# node24-stm32f765bit6.net
KiCad netlist of a schematic drawn in Altium Designer
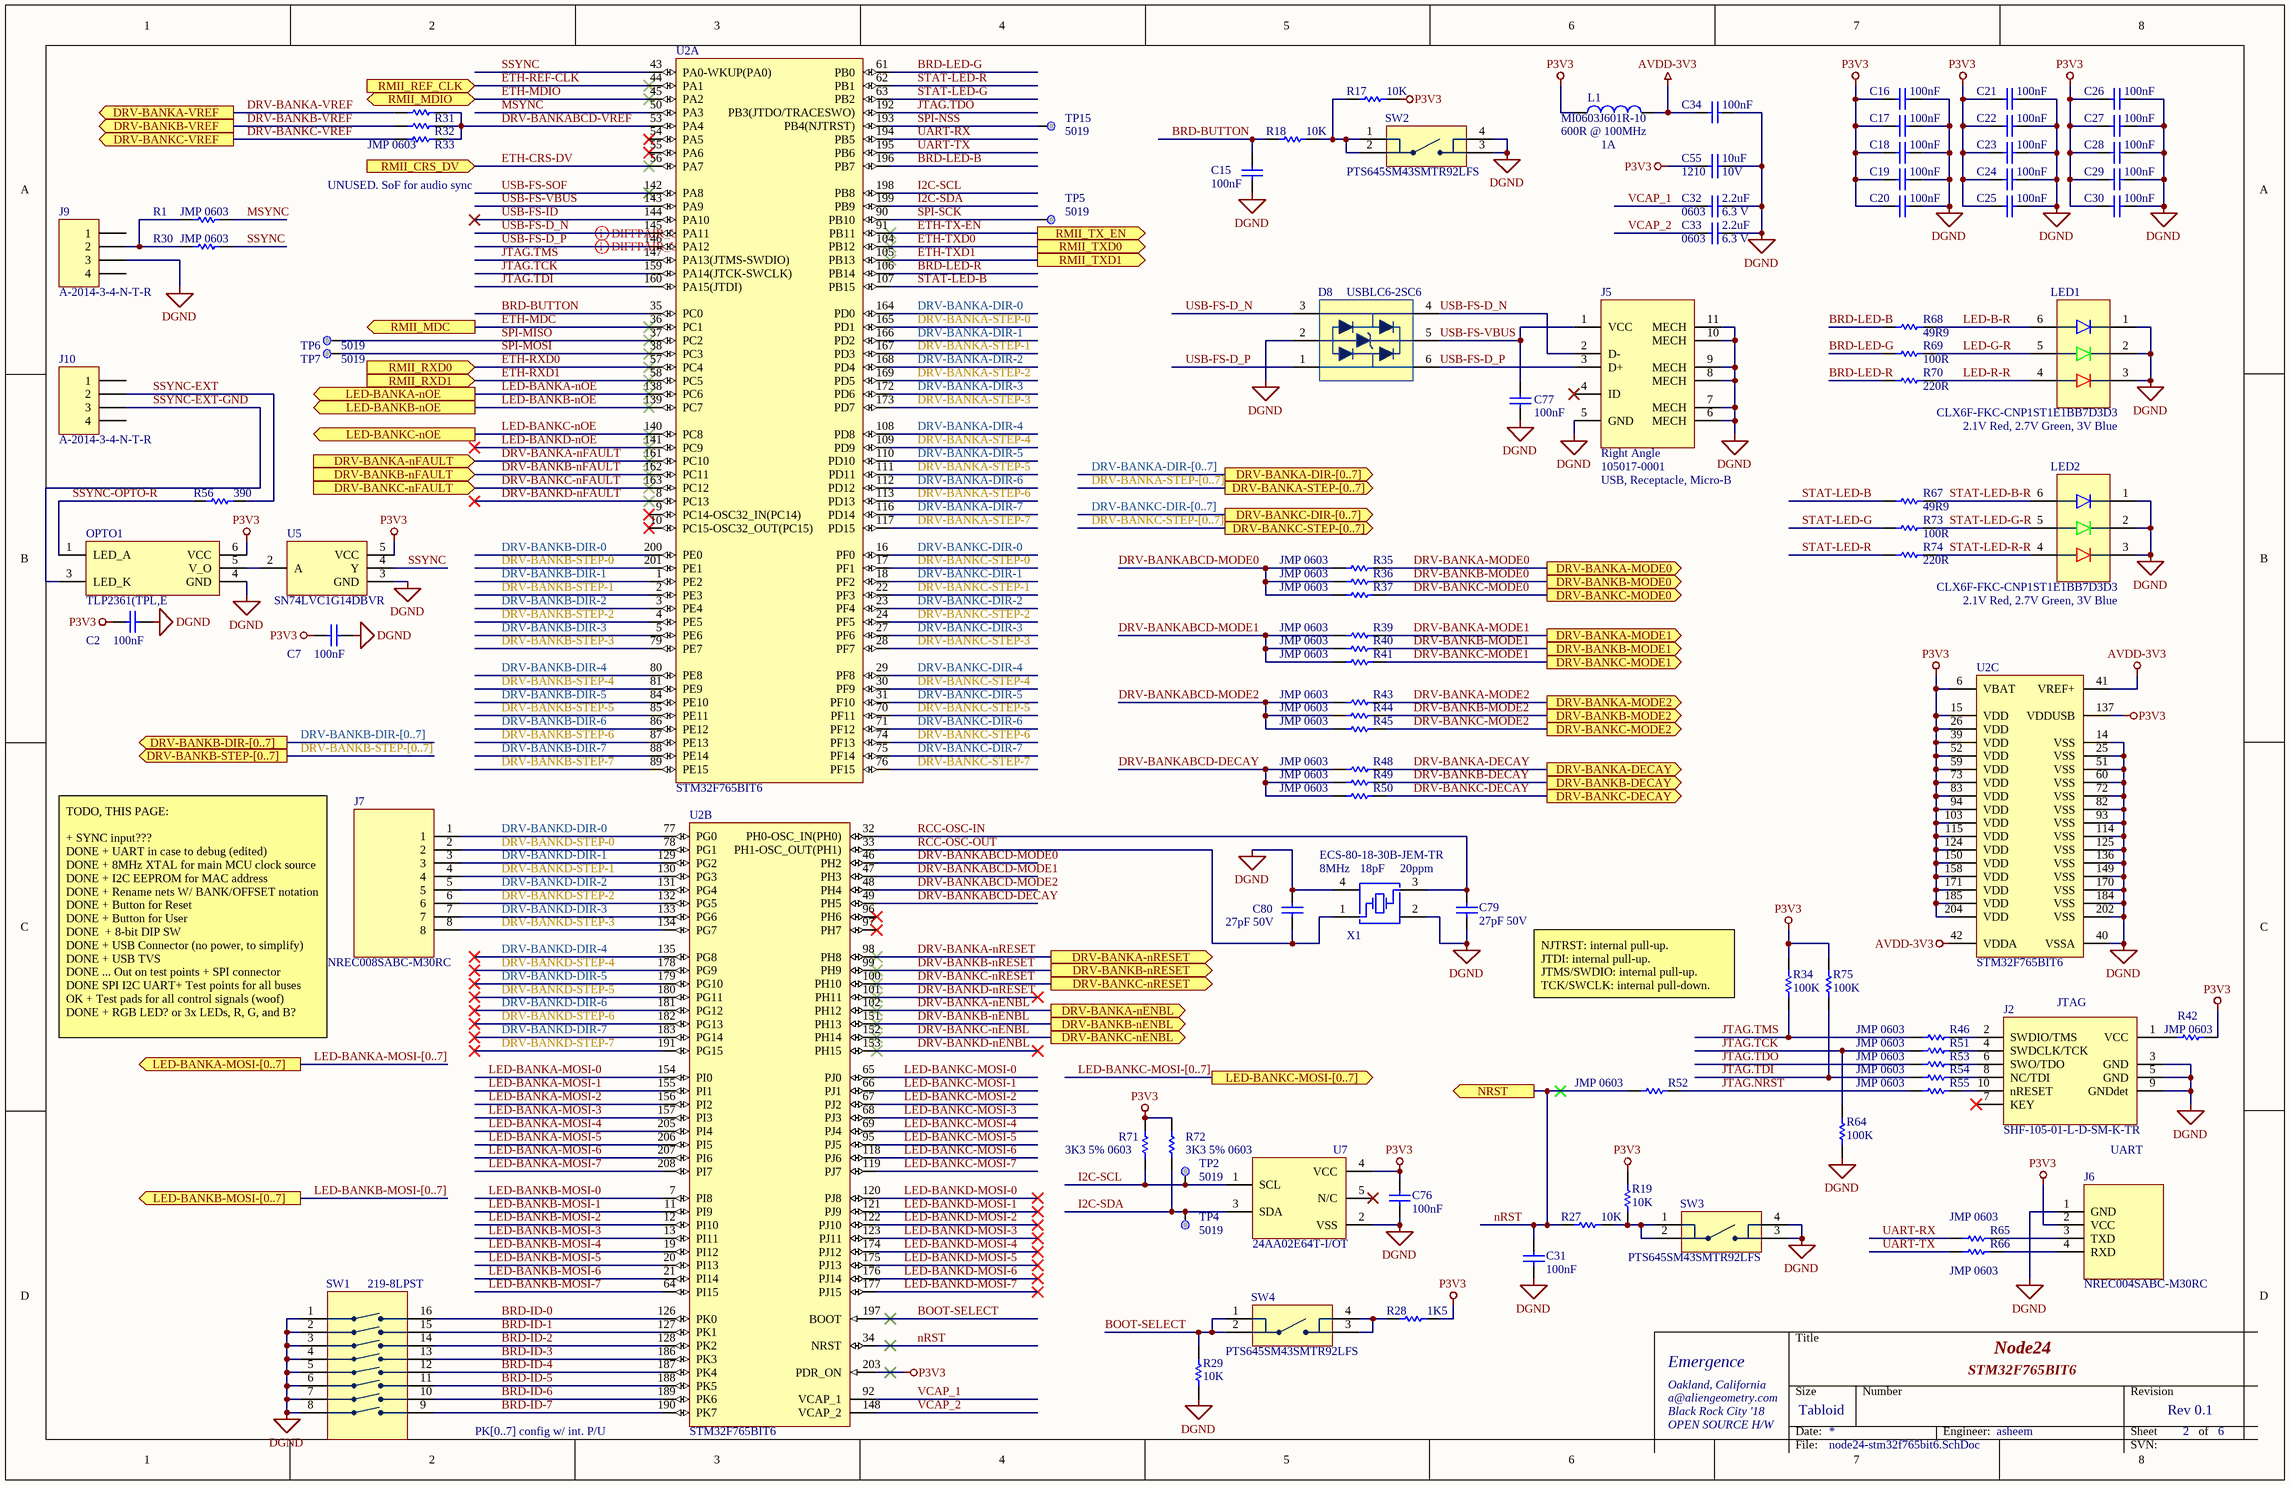
[diagram p0: node24-stm32f765bit6.SchDoc]

(export (version "E")
  (design (tool "Eeschema 10.0.6"))
  (components
    (comp (ref "C2")
      (value "100nF")
      (footprint "CAPC0603(1608)100_L")
      (description "CAP 100nF 50V ±20% 0603 (1608 Metric) Thickness 1mm SMD")
      (fields (field (name "TOLERANCE") "Â±20%"))
      (libsource (lib "Altium Content Vault") (part "CAP"))
    )
    (comp (ref "C7")
      (value "100nF")
      (footprint "CAPC0603(1608)100_L")
      (description "CAP 100nF 50V ±20% 0603 (1608 Metric) Thickness 1mm SMD")
      (fields (field (name "TOLERANCE") "Â±20%"))
      (libsource (lib "Altium Content Vault") (part "CAP"))
    )
    (comp (ref "C15")
      (value "100nF")
      (footprint "CAPC0603(1608)100_L")
      (description "CAP 100nF 50V ±20% 0603 (1608 Metric) Thickness 1mm SMD")
      (fields (field (name "TOLERANCE") "Â±20%"))
      (libsource (lib "Altium Content Vault") (part "CAP"))
    )
    (comp (ref "C16")
      (value "100nF")
      (footprint "CAPC0603(1608)100_L")
      (description "CAP 100nF 50V ±20% 0603 (1608 Metric) Thickness 1mm SMD")
      (fields (field (name "TOLERANCE") "Â±20%"))
      (libsource (lib "Altium Content Vault") (part "CAP"))
    )
    (comp (ref "C17")
      (value "100nF")
      (footprint "CAPC0603(1608)100_L")
      (description "CAP 100nF 50V ±20% 0603 (1608 Metric) Thickness 1mm SMD")
      (fields (field (name "TOLERANCE") "Â±20%"))
      (libsource (lib "Altium Content Vault") (part "CAP"))
    )
    (comp (ref "C18")
      (value "100nF")
      (footprint "CAPC0603(1608)100_L")
      (description "CAP 100nF 50V ±20% 0603 (1608 Metric) Thickness 1mm SMD")
      (fields (field (name "TOLERANCE") "Â±20%"))
      (libsource (lib "Altium Content Vault") (part "CAP"))
    )
    (comp (ref "C19")
      (value "100nF")
      (footprint "CAPC0603(1608)100_L")
      (description "CAP 100nF 50V ±20% 0603 (1608 Metric) Thickness 1mm SMD")
      (fields (field (name "TOLERANCE") "Â±20%"))
      (libsource (lib "Altium Content Vault") (part "CAP"))
    )
    (comp (ref "C20")
      (value "100nF")
      (footprint "CAPC0603(1608)100_L")
      (description "CAP 100nF 50V ±20% 0603 (1608 Metric) Thickness 1mm SMD")
      (fields (field (name "TOLERANCE") "Â±20%"))
      (libsource (lib "Altium Content Vault") (part "CAP"))
    )
    (comp (ref "C21")
      (value "100nF")
      (footprint "CAPC0603(1608)100_L")
      (description "CAP 100nF 50V ±20% 0603 (1608 Metric) Thickness 1mm SMD")
      (fields (field (name "TOLERANCE") "Â±20%"))
      (libsource (lib "Altium Content Vault") (part "CAP"))
    )
    (comp (ref "C22")
      (value "100nF")
      (footprint "CAPC0603(1608)100_L")
      (description "CAP 100nF 50V ±20% 0603 (1608 Metric) Thickness 1mm SMD")
      (fields (field (name "TOLERANCE") "Â±20%"))
      (libsource (lib "Altium Content Vault") (part "CAP"))
    )
    (comp (ref "C23")
      (value "100nF")
      (footprint "CAPC0603(1608)100_L")
      (description "CAP 100nF 50V ±20% 0603 (1608 Metric) Thickness 1mm SMD")
      (fields (field (name "TOLERANCE") "Â±20%"))
      (libsource (lib "Altium Content Vault") (part "CAP"))
    )
    (comp (ref "C24")
      (value "100nF")
      (footprint "CAPC0603(1608)100_L")
      (description "CAP 100nF 50V ±20% 0603 (1608 Metric) Thickness 1mm SMD")
      (fields (field (name "TOLERANCE") "Â±20%"))
      (libsource (lib "Altium Content Vault") (part "CAP"))
    )
    (comp (ref "C25")
      (value "100nF")
      (footprint "CAPC0603(1608)100_L")
      (description "CAP 100nF 50V ±20% 0603 (1608 Metric) Thickness 1mm SMD")
      (fields (field (name "TOLERANCE") "Â±20%"))
      (libsource (lib "Altium Content Vault") (part "CAP"))
    )
    (comp (ref "C26")
      (value "100nF")
      (footprint "CAPC0603(1608)100_L")
      (description "CAP 100nF 50V ±20% 0603 (1608 Metric) Thickness 1mm SMD")
      (fields (field (name "TOLERANCE") "Â±20%"))
      (libsource (lib "Altium Content Vault") (part "CAP"))
    )
    (comp (ref "C27")
      (value "100nF")
      (footprint "CAPC0603(1608)100_L")
      (description "CAP 100nF 50V ±20% 0603 (1608 Metric) Thickness 1mm SMD")
      (fields (field (name "TOLERANCE") "Â±20%"))
      (libsource (lib "Altium Content Vault") (part "CAP"))
    )
    (comp (ref "C28")
      (value "100nF")
      (footprint "CAPC0603(1608)100_L")
      (description "CAP 100nF 50V ±20% 0603 (1608 Metric) Thickness 1mm SMD")
      (fields (field (name "TOLERANCE") "Â±20%"))
      (libsource (lib "Altium Content Vault") (part "CAP"))
    )
    (comp (ref "C29")
      (value "100nF")
      (footprint "CAPC0603(1608)100_L")
      (description "CAP 100nF 50V ±20% 0603 (1608 Metric) Thickness 1mm SMD")
      (fields (field (name "TOLERANCE") "Â±20%"))
      (libsource (lib "Altium Content Vault") (part "CAP"))
    )
    (comp (ref "C30")
      (value "100nF")
      (footprint "CAPC0603(1608)100_L")
      (description "CAP 100nF 50V ±20% 0603 (1608 Metric) Thickness 1mm SMD")
      (fields (field (name "TOLERANCE") "Â±20%"))
      (libsource (lib "Altium Content Vault") (part "CAP"))
    )
    (comp (ref "C31")
      (value "100nF")
      (footprint "CAPC0603(1608)100_L")
      (description "CAP 100nF 50V ±20% 0603 (1608 Metric) Thickness 1mm SMD")
      (fields (field (name "TOLERANCE") "Â±20%"))
      (libsource (lib "Altium Content Vault") (part "CAP"))
    )
    (comp (ref "C32")
      (value "2.2uF")
      (footprint "CAPC0603(1608)100_M")
      (description "CAP 2.2uF 6.3V ±20% 0603 (1608 Metric) Thickness 1mm SMD")
      (fields
        (field (name "TOLERANCE") "Â±20%")
        (field (name "CASE-EIA") "0603")
        (field (name "RATED VOLTAGE") "6.3 V")
        (field (name "Comment") "2.2uF 6.3V")
      )
      (libsource (lib "Altium Content Vault") (part "CAP"))
    )
    (comp (ref "C33")
      (value "2.2uF")
      (footprint "CAPC0603(1608)100_M")
      (description "CAP 2.2uF 6.3V ±20% 0603 (1608 Metric) Thickness 1mm SMD")
      (fields
        (field (name "TOLERANCE") "Â±20%")
        (field (name "CASE-EIA") "0603")
        (field (name "RATED VOLTAGE") "6.3 V")
        (field (name "Comment") "2.2uF 6.3V")
      )
      (libsource (lib "Altium Content Vault") (part "CAP"))
    )
    (comp (ref "C34")
      (value "100nF")
      (footprint "CAPC0603(1608)100_L")
      (description "CAP 100nF 50V ±20% 0603 (1608 Metric) Thickness 1mm SMD")
      (fields (field (name "TOLERANCE") "Â±20%"))
      (libsource (lib "Altium Content Vault") (part "CAP"))
    )
    (comp (ref "C55")
      (value "CAP_CER_10UF_1210_CL32B106KPINNNE")
      (footprint "1210C")
      (description "Cap Ceramic 10uF 10V X7R 10% SMD 1210 125C Embossed T/R")
      (fields
        (field (name "MANUFACTURER") "Samsung")
        (field (name "MANUFACTURER PART NUMBER") "CL32B106KPINNNE")
        (field (name "CAPACITANCE") "10uF")
        (field (name "CASE/PACKAGE") "1210")
        (field (name "VOLTAGE RATING") "10V")
      )
      (libsource (lib "node") (part "CAP_CER_10UF_1210_CL32B106KPINNNE"))
    )
    (comp (ref "C76")
      (value "100nF")
      (footprint "CAPC0603(1608)100_L")
      (description "CAP 100nF 50V ±20% 0603 (1608 Metric) Thickness 1mm SMD")
      (fields (field (name "TOLERANCE") "Â±20%"))
      (libsource (lib "Altium Content Vault") (part "CAP"))
    )
    (comp (ref "C77")
      (value "100nF")
      (footprint "CAPC0603(1608)100_L")
      (description "CAP 100nF 50V ±20% 0603 (1608 Metric) Thickness 1mm SMD")
      (fields (field (name "TOLERANCE") "Â±20%"))
      (libsource (lib "Altium Content Vault") (part "CAP"))
    )
    (comp (ref "C79")
      (value "27pF 50V")
      (footprint "CAPC0603(1608)100_L")
      (description "CAP 27pF 50V ±5% 0603 (1608 Metric) Thickness 1mm SMD")
      (fields (field (name "TOLERANCE") "Â±5%"))
      (libsource (lib "Altium Content Vault") (part "CAP"))
    )
    (comp (ref "C80")
      (value "27pF 50V")
      (footprint "CAPC0603(1608)100_L")
      (description "CAP 27pF 50V ±5% 0603 (1608 Metric) Thickness 1mm SMD")
      (fields (field (name "TOLERANCE") "Â±5%"))
      (libsource (lib "Altium Content Vault") (part "CAP"))
    )
    (comp (ref "D8")
      (value "TVS DIODE 5.25V 17V SOT23-6")
      (footprint "SOT23-6L")
      (description "TVS DIODE 5.25VWM 17VC SOT23-6")
      (fields
        (field (name "MANUFACTURER") "STMicroelectronics")
        (field (name "MANUFACTURER PART NUMBER") "USBLC6-2SC6")
      )
      (libsource (lib "node") (part "TVS_5.25_USB_ST_USBLC6-2SC6"))
    )
    (comp (ref "J2")
      (value "CONN_HDR_2X5_V_M_SM_50MIL_SAMTEC_SHF-105-01-L-D-SM-K-TR")
      (footprint "CONN_SAMTEC_HDR_50MIL_10POS_SHRD_SM_SHF-105-01-L-D-SM")
      (description "Conn Shrouded Header HDR 10 POS 1.27mm Solder ST SMD T/R")
      (fields
        (field (name "MANUFACTURER") "Samtec")
        (field (name "MANUFACTURER PART NUMBER") "SHF-105-01-L-D-SM-K-TR")
      )
      (libsource (lib "node") (part "CONN_HDR_2X5_V_M_SM_50MIL_SAMTEC_SHF-105-01-L-D-SM-K-TR"))
    )
    (comp (ref "J5")
      (value "CONN_USB_MICRO-B_RA_SMD_MOLEX_105017-0001")
      (footprint "CONN_MOLEX_USB_MICRO_B_SMD_RA_1050170001")
      (description "USB - micro B  Receptacle Connector 5 Position Board Cutout, Surface Mount, Right Angle")
      (fields
        (field (name "MANUFACTURER") "Molex")
        (field (name "ORIENTATION") "Right Angle")
        (field (name "MANUFACTURER PART NUMBER") "105017-0001")
        (field (name "CONNECTOR TYPE") "USB, Receptacle, Micro-B")
      )
      (libsource (lib "node") (part "CONN_USB_MICRO-B_RA_SMD_MOLEX_105017-0001"))
    )
    (comp (ref "J6")
      (value "CONN_HDR_1X4_V_SMT_NREC004SABC-M30RC")
      (footprint "HDR_1X4_2R54_V_M_SMT")
      (description "CONN HEADER .100\" SNGL SMD 4POS")
      (fields
        (field (name "MANUFACTURER") "Sullins")
        (field (name "MANUFACTURER PART NUMBER") "NREC004SABC-M30RC")
      )
      (libsource (lib "node") (part "CONN_HDR_1X4_V_SMT_NREC004SABC-M30RC"))
    )
    (comp (ref "J7")
      (value "CONN_HDR_1X8_V_M_SMT_NREC008SABC-M30RC")
      (footprint "HDR_1X8_2R54_V_M_SMT")
      (description "8 Positions Header, Unshrouded Connector 0.100\" (2.54mm) Surface Mount Tin")
      (fields
        (field (name "MANUFACTURER") "Sullins")
        (field (name "MANUFACTURER PART NUMBER") "NREC008SABC-M30RC")
      )
      (libsource (lib "node") (part "CONN_HDR_1X8_V_M_SMT_NREC008SABC-M30RC"))
    )
    (comp (ref "J9")
      (value "CONN_ASSMANN_JACK_MOD_4P4C_A-2014-3-4-N-T-R")
      (footprint "CON_JACK_MOD_4P4C_ASSMANN_A-2014-3-4-N-T-R")
      (description "CONN MOD JACK 4P4C VERT")
      (fields
        (field (name "MANUFACTURER") "Assmann")
        (field (name "MANUFACTURER PART NUMBER") "A-2014-3-4-N-T-R")
      )
      (libsource (lib "node") (part "CONN_ASSMANN_JACK_MOD_4P4C_A-2014-3-4-N-T-R"))
    )
    (comp (ref "J10")
      (value "CONN_ASSMANN_JACK_MOD_4P4C_A-2014-3-4-N-T-R")
      (footprint "CON_JACK_MOD_4P4C_ASSMANN_A-2014-3-4-N-T-R")
      (description "CONN MOD JACK 4P4C VERT")
      (fields
        (field (name "MANUFACTURER") "Assmann")
        (field (name "MANUFACTURER PART NUMBER") "A-2014-3-4-N-T-R")
      )
      (libsource (lib "node") (part "CONN_ASSMANN_JACK_MOD_4P4C_A-2014-3-4-N-T-R"))
    )
    (comp (ref "L1")
      (value "BEAD_LAIRD_MI0603J601R-10")
      (footprint "0603L")
      (description "FERRITE BEAD 600 OHM 0603")
      (fields
        (field (name "MANUFACTURER") "Laird")
        (field (name "MANUFACTURER PART NUMBER") "MI0603J601R-10")
        (field (name "MAX DC CURRENT") "1A")
        (field (name "IMPEDANCE") "600R @ 100MHz")
      )
      (libsource (lib "node") (part "BEAD_LAIRD_MI0603J601R-10"))
    )
    (comp (ref "LED1")
      (value "LED_RGB_SMD_CLX6F-FKC-CNP1ST1E1BB7D3D3")
      (footprint "LED_6PLCC_RGB")
      (description "LED RGB IPX8 6PLCC 3.5X3.4X2.8MM")
      (fields
        (field (name "MANUFACTURER") "Cree")
        (field (name "FORWARD VOLTAGE") "2.1V Red, 2.7V Green, 3V Blue")
        (field (name "MANUFACTURER PART NUMBER") "CLX6F-FKC-CNP1ST1E1BB7D3D3")
      )
      (libsource (lib "node") (part "LED_RGB_SMD_CLX6F-FKC-CNP1ST1E1BB7D3D3"))
    )
    (comp (ref "LED2")
      (value "LED_RGB_SMD_CLX6F-FKC-CNP1ST1E1BB7D3D3")
      (footprint "LED_6PLCC_RGB")
      (description "LED RGB IPX8 6PLCC 3.5X3.4X2.8MM")
      (fields
        (field (name "MANUFACTURER") "Cree")
        (field (name "FORWARD VOLTAGE") "2.1V Red, 2.7V Green, 3V Blue")
        (field (name "MANUFACTURER PART NUMBER") "CLX6F-FKC-CNP1ST1E1BB7D3D3")
      )
      (libsource (lib "node") (part "LED_RGB_SMD_CLX6F-FKC-CNP1ST1E1BB7D3D3"))
    )
    (comp (ref "OPTO1")
      (value "OPTO_TOSHIBA_LOGIC_PUSHPULL_TLP2361(TPL,E")
      (footprint "SO-5")
      (description "Optocoupler Logic-Out Totem-Pole DC-IN 1-CH 5-Pin SO T/R")
      (fields
        (field (name "MANUFACTURER") "Toshiba")
        (field (name "MANUFACTURER PART NUMBER") "TLP2361(TPL,E")
      )
      (libsource (lib "node") (part "OPTO_TOSHIBA_LOGIC_PUSHPULL_TLP2361(TPL,E"))
    )
    (comp (ref "R1")
      (value "JMP 0603")
      (footprint "RESC0603(1608)_L")
      (description "Jumper 0603 (1608 Metric)")
      (fields (field (name "POWER") "None"))
      (libsource (lib "Altium Content Vault") (part "RES"))
    )
    (comp (ref "R17")
      (value "10K")
      (footprint "RESC0603(1608)_L")
      (description "10K 0.1W 1% 0603 (1608 Metric)  SMD")
      (fields (field (name "POWER") "0.1 W") (field (name "TOLERANCE") "1 %"))
      (libsource (lib "Altium Content Vault") (part "RES"))
    )
    (comp (ref "R18")
      (value "10K")
      (footprint "RESC0603(1608)_L")
      (description "10K 0.1W 1% 0603 (1608 Metric)  SMD")
      (fields (field (name "POWER") "0.1 W") (field (name "TOLERANCE") "1 %"))
      (libsource (lib "Altium Content Vault") (part "RES"))
    )
    (comp (ref "R19")
      (value "10K")
      (footprint "RESC0603(1608)_L")
      (description "10K 0.1W 1% 0603 (1608 Metric)  SMD")
      (fields (field (name "POWER") "0.1 W") (field (name "TOLERANCE") "1 %"))
      (libsource (lib "Altium Content Vault") (part "RES"))
    )
    (comp (ref "R27")
      (value "10K")
      (footprint "RESC0603(1608)_L")
      (description "10K 0.1W 1% 0603 (1608 Metric)  SMD")
      (fields (field (name "POWER") "0.1 W") (field (name "TOLERANCE") "1 %"))
      (libsource (lib "Altium Content Vault") (part "RES"))
    )
    (comp (ref "R28")
      (value "1K5")
      (footprint "RESC0603(1608)_L")
      (description "1K5 0.1W 1% 0603 (1608 Metric)  SMD")
      (fields (field (name "POWER") "0.1 W") (field (name "TOLERANCE") "1 %"))
      (libsource (lib "Altium Content Vault") (part "RES"))
    )
    (comp (ref "R29")
      (value "10K")
      (footprint "RESC0603(1608)_L")
      (description "10K 0.1W 1% 0603 (1608 Metric)  SMD")
      (fields (field (name "POWER") "0.1 W") (field (name "TOLERANCE") "1 %"))
      (libsource (lib "Altium Content Vault") (part "RES"))
    )
    (comp (ref "R30")
      (value "JMP 0603")
      (footprint "RESC0603(1608)_L")
      (description "Jumper 0603 (1608 Metric)")
      (fields (field (name "POWER") "None"))
      (libsource (lib "Altium Content Vault") (part "RES"))
    )
    (comp (ref "R31")
      (value "JMP 0603")
      (footprint "RESC0603(1608)_L")
      (description "Jumper 0603 (1608 Metric)")
      (fields (field (name "POWER") "None"))
      (libsource (lib "Altium Content Vault") (part "RES"))
    )
    (comp (ref "R32")
      (value "JMP 0603")
      (footprint "RESC0603(1608)_L")
      (description "Jumper 0603 (1608 Metric)")
      (fields (field (name "POWER") "None"))
      (libsource (lib "Altium Content Vault") (part "RES"))
    )
    (comp (ref "R33")
      (value "JMP 0603")
      (footprint "RESC0603(1608)_L")
      (description "Jumper 0603 (1608 Metric)")
      (fields (field (name "POWER") "None"))
      (libsource (lib "Altium Content Vault") (part "RES"))
    )
    (comp (ref "R34")
      (value "100K")
      (footprint "RESC0603(1608)_L")
      (description "100K 0.1W 1% 0603 (1608 Metric)  SMD")
      (fields (field (name "POWER") "0.1 W") (field (name "TOLERANCE") "1 %"))
      (libsource (lib "Altium Content Vault") (part "RES"))
    )
    (comp (ref "R35")
      (value "JMP 0603")
      (footprint "RESC0603(1608)_L")
      (description "Jumper 0603 (1608 Metric)")
      (fields (field (name "POWER") "None"))
      (libsource (lib "Altium Content Vault") (part "RES"))
    )
    (comp (ref "R36")
      (value "JMP 0603")
      (footprint "RESC0603(1608)_L")
      (description "Jumper 0603 (1608 Metric)")
      (fields (field (name "POWER") "None"))
      (libsource (lib "Altium Content Vault") (part "RES"))
    )
    (comp (ref "R37")
      (value "JMP 0603")
      (footprint "RESC0603(1608)_L")
      (description "Jumper 0603 (1608 Metric)")
      (fields (field (name "POWER") "None"))
      (libsource (lib "Altium Content Vault") (part "RES"))
    )
    (comp (ref "R39")
      (value "JMP 0603")
      (footprint "RESC0603(1608)_L")
      (description "Jumper 0603 (1608 Metric)")
      (fields (field (name "POWER") "None"))
      (libsource (lib "Altium Content Vault") (part "RES"))
    )
    (comp (ref "R40")
      (value "JMP 0603")
      (footprint "RESC0603(1608)_L")
      (description "Jumper 0603 (1608 Metric)")
      (fields (field (name "POWER") "None"))
      (libsource (lib "Altium Content Vault") (part "RES"))
    )
    (comp (ref "R41")
      (value "JMP 0603")
      (footprint "RESC0603(1608)_L")
      (description "Jumper 0603 (1608 Metric)")
      (fields (field (name "POWER") "None"))
      (libsource (lib "Altium Content Vault") (part "RES"))
    )
    (comp (ref "R42")
      (value "JMP 0603")
      (footprint "RESC0603(1608)_L")
      (description "Jumper 0603 (1608 Metric)")
      (fields (field (name "POWER") "None"))
      (libsource (lib "Altium Content Vault") (part "RES"))
    )
    (comp (ref "R43")
      (value "JMP 0603")
      (footprint "RESC0603(1608)_L")
      (description "Jumper 0603 (1608 Metric)")
      (fields (field (name "POWER") "None"))
      (libsource (lib "Altium Content Vault") (part "RES"))
    )
    (comp (ref "R44")
      (value "JMP 0603")
      (footprint "RESC0603(1608)_L")
      (description "Jumper 0603 (1608 Metric)")
      (fields (field (name "POWER") "None"))
      (libsource (lib "Altium Content Vault") (part "RES"))
    )
    (comp (ref "R45")
      (value "JMP 0603")
      (footprint "RESC0603(1608)_L")
      (description "Jumper 0603 (1608 Metric)")
      (fields (field (name "POWER") "None"))
      (libsource (lib "Altium Content Vault") (part "RES"))
    )
    (comp (ref "R46")
      (value "JMP 0603")
      (footprint "RESC0603(1608)_L")
      (description "Jumper 0603 (1608 Metric)")
      (fields (field (name "POWER") "None"))
      (libsource (lib "Altium Content Vault") (part "RES"))
    )
    (comp (ref "R48")
      (value "JMP 0603")
      (footprint "RESC0603(1608)_L")
      (description "Jumper 0603 (1608 Metric)")
      (fields (field (name "POWER") "None"))
      (libsource (lib "Altium Content Vault") (part "RES"))
    )
    (comp (ref "R49")
      (value "JMP 0603")
      (footprint "RESC0603(1608)_L")
      (description "Jumper 0603 (1608 Metric)")
      (fields (field (name "POWER") "None"))
      (libsource (lib "Altium Content Vault") (part "RES"))
    )
    (comp (ref "R50")
      (value "JMP 0603")
      (footprint "RESC0603(1608)_L")
      (description "Jumper 0603 (1608 Metric)")
      (fields (field (name "POWER") "None"))
      (libsource (lib "Altium Content Vault") (part "RES"))
    )
    (comp (ref "R51")
      (value "JMP 0603")
      (footprint "RESC0603(1608)_L")
      (description "Jumper 0603 (1608 Metric)")
      (fields (field (name "POWER") "None"))
      (libsource (lib "Altium Content Vault") (part "RES"))
    )
    (comp (ref "R52")
      (value "JMP 0603")
      (footprint "RESC0603(1608)_L")
      (description "Jumper 0603 (1608 Metric)")
      (fields (field (name "POWER") "None"))
      (libsource (lib "Altium Content Vault") (part "RES"))
    )
    (comp (ref "R53")
      (value "JMP 0603")
      (footprint "RESC0603(1608)_L")
      (description "Jumper 0603 (1608 Metric)")
      (fields (field (name "POWER") "None"))
      (libsource (lib "Altium Content Vault") (part "RES"))
    )
    (comp (ref "R54")
      (value "JMP 0603")
      (footprint "RESC0603(1608)_L")
      (description "Jumper 0603 (1608 Metric)")
      (fields (field (name "POWER") "None"))
      (libsource (lib "Altium Content Vault") (part "RES"))
    )
    (comp (ref "R55")
      (value "JMP 0603")
      (footprint "RESC0603(1608)_L")
      (description "Jumper 0603 (1608 Metric)")
      (fields (field (name "POWER") "None"))
      (libsource (lib "Altium Content Vault") (part "RES"))
    )
    (comp (ref "R56")
      (value "390")
      (footprint "RESC0603(1608)_L")
      (description "390R 0.1W 1% 0603 (1608 Metric)  SMD")
      (fields (field (name "POWER") "0.1 W") (field (name "TOLERANCE") "1 %"))
      (libsource (lib "Altium Content Vault") (part "RES"))
    )
    (comp (ref "R64")
      (value "100K")
      (footprint "RESC0603(1608)_L")
      (description "100K 0.1W 1% 0603 (1608 Metric)  SMD")
      (fields (field (name "POWER") "0.1 W") (field (name "TOLERANCE") "1 %"))
      (libsource (lib "Altium Content Vault") (part "RES"))
    )
    (comp (ref "R65")
      (value "JMP 0603")
      (footprint "RESC0603(1608)_L")
      (description "Jumper 0603 (1608 Metric)")
      (fields (field (name "POWER") "None"))
      (libsource (lib "Altium Content Vault") (part "RES"))
    )
    (comp (ref "R66")
      (value "JMP 0603")
      (footprint "RESC0603(1608)_L")
      (description "Jumper 0603 (1608 Metric)")
      (fields (field (name "POWER") "None"))
      (libsource (lib "Altium Content Vault") (part "RES"))
    )
    (comp (ref "R67")
      (value "49R9")
      (footprint "RESC0603(1608)_L")
      (description "49R9 0.1W 1% 0603 (1608 Metric)  SMD")
      (fields (field (name "POWER") "0.1 W") (field (name "TOLERANCE") "1 %"))
      (libsource (lib "Altium Content Vault") (part "RES"))
    )
    (comp (ref "R68")
      (value "49R9")
      (footprint "RESC0603(1608)_L")
      (description "49R9 0.1W 1% 0603 (1608 Metric)  SMD")
      (fields (field (name "POWER") "0.1 W") (field (name "TOLERANCE") "1 %"))
      (libsource (lib "Altium Content Vault") (part "RES"))
    )
    (comp (ref "R69")
      (value "100R")
      (footprint "RESC0603(1608)_L")
      (description "100R 0.1W 1% 0603 (1608 Metric)  SMD")
      (fields (field (name "TOLERANCE") "1 %") (field (name "POWER") "0.1 W"))
      (libsource (lib "Altium Content Vault") (part "RES"))
    )
    (comp (ref "R70")
      (value "220R")
      (footprint "RESC0603(1608)_L")
      (description "220R 0.1W 1% 0603 (1608 Metric)  SMD")
      (fields (field (name "TOLERANCE") "1 %") (field (name "POWER") "0.1 W"))
      (libsource (lib "Altium Content Vault") (part "RES"))
    )
    (comp (ref "R71")
      (value "3K3 5% 0603")
      (footprint "RESC0603(1608)_L")
      (description "3K3 0.1W 5% 0603 (1608 Metric)  SMD")
      (fields (field (name "TOLERANCE") "5 %") (field (name "POWER") "0.1 W"))
      (libsource (lib "Altium Content Vault") (part "RES"))
    )
    (comp (ref "R72")
      (value "3K3 5% 0603")
      (footprint "RESC0603(1608)_L")
      (description "3K3 0.1W 5% 0603 (1608 Metric)  SMD")
      (fields (field (name "TOLERANCE") "5 %") (field (name "POWER") "0.1 W"))
      (libsource (lib "Altium Content Vault") (part "RES"))
    )
    (comp (ref "R73")
      (value "100R")
      (footprint "RESC0603(1608)_L")
      (description "100R 0.1W 1% 0603 (1608 Metric)  SMD")
      (fields (field (name "TOLERANCE") "1 %") (field (name "POWER") "0.1 W"))
      (libsource (lib "Altium Content Vault") (part "RES"))
    )
    (comp (ref "R74")
      (value "220R")
      (footprint "RESC0603(1608)_L")
      (description "220R 0.1W 1% 0603 (1608 Metric)  SMD")
      (fields (field (name "TOLERANCE") "1 %") (field (name "POWER") "0.1 W"))
      (libsource (lib "Altium Content Vault") (part "RES"))
    )
    (comp (ref "R75")
      (value "100K")
      (footprint "RESC0603(1608)_L")
      (description "100K 0.1W 1% 0603 (1608 Metric)  SMD")
      (fields (field (name "POWER") "0.1 W") (field (name "TOLERANCE") "1 %"))
      (libsource (lib "Altium Content Vault") (part "RES"))
    )
    (comp (ref "SW1")
      (value "SWITCH_CTS_DIP_8BIT_SMD_219-8LPST")
      (footprint "SWITCH_DIP_CTS_8-BIT_219-8LPST")
      (description "Switch DIP ON OFF SPST 8 Flush Slide 0.1A 20VDC Gull Wing 2.54mm SMD Tube")
      (fields (field (name "MANUFACTURER") "CTS") (field (name "MANUFACTURER PART NUMBER") "219-8LPST"))
      (libsource (lib "node") (part "SWITCH_CTS_DIP_8BIT_SMD_219-8LPST"))
    )
    (comp (ref "SW2")
      (value "SWITCH_CK_TACTILE_SPST_SMD_PTS645SM43SMTR92LFS")
      (footprint "SWITCH_CK_TACT_PTS645SM43SMTR92")
      (description "SWITCH TACTILE SPST-NO 0.05A 12V")
      (fields
        (field (name "MANUFACTURER") "ITT C&K")
        (field (name "MANUFACTURER PART NUMBER") "PTS645SM43SMTR92LFS")
      )
      (libsource (lib "node") (part "SWITCH_CK_TACTILE_SPST_SMD_PTS645SM43SMTR92LFS"))
    )
    (comp (ref "SW3")
      (value "SWITCH_CK_TACTILE_SPST_SMD_PTS645SM43SMTR92LFS")
      (footprint "SWITCH_CK_TACT_PTS645SM43SMTR92")
      (description "SWITCH TACTILE SPST-NO 0.05A 12V")
      (fields
        (field (name "MANUFACTURER") "ITT C&K")
        (field (name "MANUFACTURER PART NUMBER") "PTS645SM43SMTR92LFS")
      )
      (libsource (lib "node") (part "SWITCH_CK_TACTILE_SPST_SMD_PTS645SM43SMTR92LFS"))
    )
    (comp (ref "SW4")
      (value "SWITCH_CK_TACTILE_SPST_SMD_PTS645SM43SMTR92LFS")
      (footprint "SWITCH_CK_TACT_PTS645SM43SMTR92")
      (description "SWITCH TACTILE SPST-NO 0.05A 12V")
      (fields
        (field (name "MANUFACTURER") "ITT C&K")
        (field (name "MANUFACTURER PART NUMBER") "PTS645SM43SMTR92LFS")
      )
      (libsource (lib "node") (part "SWITCH_CK_TACTILE_SPST_SMD_PTS645SM43SMTR92LFS"))
    )
    (comp (ref "TP2")
      (value "TEST_POINT_KEYSTONE_5019_SMT")
      (footprint "TEST_POINT_KEYSTONE_5019")
      (description "Circuit Board Hardware - PCB TEST POINT")
      (fields
        (field (name "MANUFACTURER") "Keystone Electronics")
        (field (name "MANUFACTURER PART NUMBER") "5019")
      )
      (libsource (lib "node") (part "TEST_POINT_KEYSTONE_5019_SMT"))
    )
    (comp (ref "TP4")
      (value "TEST_POINT_KEYSTONE_5019_SMT")
      (footprint "TEST_POINT_KEYSTONE_5019")
      (description "Circuit Board Hardware - PCB TEST POINT")
      (fields
        (field (name "MANUFACTURER") "Keystone Electronics")
        (field (name "MANUFACTURER PART NUMBER") "5019")
      )
      (libsource (lib "node") (part "TEST_POINT_KEYSTONE_5019_SMT"))
    )
    (comp (ref "TP5")
      (value "TEST_POINT_KEYSTONE_5019_SMT")
      (footprint "TEST_POINT_KEYSTONE_5019")
      (description "Circuit Board Hardware - PCB TEST POINT")
      (fields
        (field (name "MANUFACTURER") "Keystone Electronics")
        (field (name "MANUFACTURER PART NUMBER") "5019")
      )
      (libsource (lib "node") (part "TEST_POINT_KEYSTONE_5019_SMT"))
    )
    (comp (ref "TP6")
      (value "TEST_POINT_KEYSTONE_5019_SMT")
      (footprint "TEST_POINT_KEYSTONE_5019")
      (description "Circuit Board Hardware - PCB TEST POINT")
      (fields
        (field (name "MANUFACTURER") "Keystone Electronics")
        (field (name "MANUFACTURER PART NUMBER") "5019")
      )
      (libsource (lib "node") (part "TEST_POINT_KEYSTONE_5019_SMT"))
    )
    (comp (ref "TP7")
      (value "TEST_POINT_KEYSTONE_5019_SMT")
      (footprint "TEST_POINT_KEYSTONE_5019")
      (description "Circuit Board Hardware - PCB TEST POINT")
      (fields
        (field (name "MANUFACTURER") "Keystone Electronics")
        (field (name "MANUFACTURER PART NUMBER") "5019")
      )
      (libsource (lib "node") (part "TEST_POINT_KEYSTONE_5019_SMT"))
    )
    (comp (ref "TP15")
      (value "TEST_POINT_KEYSTONE_5019_SMT")
      (footprint "TEST_POINT_KEYSTONE_5019")
      (description "Circuit Board Hardware - PCB TEST POINT")
      (fields
        (field (name "MANUFACTURER") "Keystone Electronics")
        (field (name "MANUFACTURER PART NUMBER") "5019")
      )
      (libsource (lib "node") (part "TEST_POINT_KEYSTONE_5019_SMT"))
    )
    (comp (ref "U2")
      (value "STM32F765BIT6")
      (footprint "QFP208L_B28X28_P0MM5")
      (description "IC MCU 32BIT 2MB FLASH 208LQFP")
      (fields
        (field (name "MANUFACTURER") "STMicroelectronics")
        (field (name "MANUFACTURER PART NUMBER") "STM32F765BIT6")
      )
      (libsource (lib "node") (part "IC_PROCESSOR_STM_STM32F765BIT6_LQFP208"))
    )
    (comp (ref "U5")
      (value "LOGIC_INVERTER_SN74LVC1G14DBVR")
      (footprint "SOT-23-5L")
      (description "IC SCHMITT TRIG INV SOT-23-5")
      (fields
        (field (name "MANUFACTURER") "Texas Instruments")
        (field (name "MANUFACTURER PART NUMBER") "SN74LVC1G14DBVR")
      )
      (libsource (lib "node") (part "LOGIC_INVERTER_SN74LVC1G14DBVR"))
    )
    (comp (ref "U7")
      (value "IC EEPROM 2K I2C 400KHZ SOT23-5")
      (footprint "SOT-23-5L")
      (description "IC EEPROM 2KBIT 400KHZ SOT23-5")
      (fields
        (field (name "MANUFACTURER") "Microchip")
        (field (name "MANUFACTURER PART NUMBER") "24AA02E64T-I/OT")
      )
      (libsource (lib "node") (part "EEPROM_I2C_2KB_MAC_24AA02E64T-I/OT"))
    )
    (comp (ref "X1")
      (value "XTAL_8MHz_4SMD_18PF_20PPM_ECS-80-18-30B-JEM-TR")
      (footprint "XTAL_4SMD_5x3mm2")
      (description "8MHz ±20ppm Crystal 18pF 100 Ohm -20°C ~ 70°C  Surface Mount 4-SMD, No Lead (DFN, LCC)")
      (fields
        (field (name "MANUFACTURER") "ECS International")
        (field (name "LOAD CAPACITANCE") "18pF")
        (field (name "FREQUENCY TOLERANCE") "20ppm")
        (field (name "FREQUENCY") "8MHz")
        (field (name "MANUFACTURER PART NUMBER") "ECS-80-18-30B-JEM-TR")
      )
      (libsource (lib "node") (part "XTAL_8MHz_4SMD_18PF_20PPM_ECS-80-18-30B-JEM-TR"))
    )
  )
  (nets
    (net (code "1") (name "/BOOT-SELECT") (class "Default")
      (node (ref "R29") (pin "2") (pinfunction "2_2") (pintype "passive"))
      (node (ref "SW4") (pin "1") (pinfunction "1_1") (pintype "passive"))
      (node (ref "SW4") (pin "2") (pinfunction "2_2") (pintype "passive"))
      (node (ref "U2") (pin "197") (pinfunction "BOOT_197") (pintype "input"))
    )
    (net (code "2") (name "/BRD-BUTTON") (class "Default")
      (node (ref "C15") (pin "2") (pinfunction "2_2") (pintype "passive"))
      (node (ref "R18") (pin "1") (pinfunction "1_1") (pintype "passive"))
      (node (ref "U2") (pin "35") (pinfunction "PC0_35") (pintype "bidirectional"))
    )
    (net (code "3") (name "/BRD-ID-0") (class "Default")
      (node (ref "SW1") (pin "16") (pinfunction "16_16") (pintype "passive"))
      (node (ref "U2") (pin "126") (pinfunction "PK0_126") (pintype "bidirectional"))
    )
    (net (code "4") (name "/BRD-ID-1") (class "Default")
      (node (ref "SW1") (pin "15") (pinfunction "15_15") (pintype "passive"))
      (node (ref "U2") (pin "127") (pinfunction "PK1_127") (pintype "bidirectional"))
    )
    (net (code "5") (name "/BRD-ID-2") (class "Default")
      (node (ref "SW1") (pin "14") (pinfunction "14_14") (pintype "passive"))
      (node (ref "U2") (pin "128") (pinfunction "PK2_128") (pintype "bidirectional"))
    )
    (net (code "6") (name "/BRD-ID-3") (class "Default")
      (node (ref "SW1") (pin "13") (pinfunction "13_13") (pintype "passive"))
      (node (ref "U2") (pin "186") (pinfunction "PK3_186") (pintype "bidirectional"))
    )
    (net (code "7") (name "/BRD-ID-4") (class "Default")
      (node (ref "SW1") (pin "12") (pinfunction "12_12") (pintype "passive"))
      (node (ref "U2") (pin "187") (pinfunction "PK4_187") (pintype "bidirectional"))
    )
    (net (code "8") (name "/BRD-ID-5") (class "Default")
      (node (ref "SW1") (pin "11") (pinfunction "11_11") (pintype "passive"))
      (node (ref "U2") (pin "188") (pinfunction "PK5_188") (pintype "bidirectional"))
    )
    (net (code "9") (name "/BRD-ID-6") (class "Default")
      (node (ref "SW1") (pin "10") (pinfunction "10_10") (pintype "passive"))
      (node (ref "U2") (pin "189") (pinfunction "PK6_189") (pintype "bidirectional"))
    )
    (net (code "10") (name "/BRD-ID-7") (class "Default")
      (node (ref "SW1") (pin "9") (pinfunction "9_9") (pintype "passive"))
      (node (ref "U2") (pin "190") (pinfunction "PK7_190") (pintype "bidirectional"))
    )
    (net (code "11") (name "/BRD-LED-B") (class "Default")
      (node (ref "R68") (pin "2") (pinfunction "2_2") (pintype "passive"))
      (node (ref "U2") (pin "196") (pinfunction "PB7_196") (pintype "bidirectional"))
    )
    (net (code "12") (name "/BRD-LED-G") (class "Default")
      (node (ref "R69") (pin "1") (pinfunction "1_1") (pintype "passive"))
      (node (ref "U2") (pin "61") (pinfunction "PB0_61") (pintype "bidirectional"))
    )
    (net (code "13") (name "/BRD-LED-R") (class "Default")
      (node (ref "R70") (pin "2") (pinfunction "2_2") (pintype "passive"))
      (node (ref "U2") (pin "106") (pinfunction "PB14_106") (pintype "bidirectional"))
    )
    (net (code "14") (name "/DRV-BANKA-DECAY") (class "Default")
      (node (ref "R48") (pin "2") (pinfunction "2_2") (pintype "passive"))
    )
    (net (code "15") (name "/DRV-BANKA-DIR-0") (class "Default")
      (node (ref "U2") (pin "164") (pinfunction "PD0_164") (pintype "bidirectional"))
    )
    (net (code "16") (name "/DRV-BANKA-DIR-1") (class "Default")
      (node (ref "U2") (pin "166") (pinfunction "PD2_166") (pintype "bidirectional"))
    )
    (net (code "17") (name "/DRV-BANKA-DIR-2") (class "Default")
      (node (ref "U2") (pin "168") (pinfunction "PD4_168") (pintype "bidirectional"))
    )
    (net (code "18") (name "/DRV-BANKA-DIR-3") (class "Default")
      (node (ref "U2") (pin "172") (pinfunction "PD6_172") (pintype "bidirectional"))
    )
    (net (code "19") (name "/DRV-BANKA-DIR-4") (class "Default")
      (node (ref "U2") (pin "108") (pinfunction "PD8_108") (pintype "bidirectional"))
    )
    (net (code "20") (name "/DRV-BANKA-DIR-5") (class "Default")
      (node (ref "U2") (pin "110") (pinfunction "PD10_110") (pintype "bidirectional"))
    )
    (net (code "21") (name "/DRV-BANKA-DIR-6") (class "Default")
      (node (ref "U2") (pin "112") (pinfunction "PD12_112") (pintype "bidirectional"))
    )
    (net (code "22") (name "/DRV-BANKA-DIR-7") (class "Default")
      (node (ref "U2") (pin "116") (pinfunction "PD14_116") (pintype "bidirectional"))
    )
    (net (code "24") (name "/DRV-BANKA-MODE0") (class "Default")
      (node (ref "R35") (pin "2") (pinfunction "2_2") (pintype "passive"))
    )
    (net (code "25") (name "/DRV-BANKA-MODE1") (class "Default")
      (node (ref "R39") (pin "2") (pinfunction "2_2") (pintype "passive"))
    )
    (net (code "26") (name "/DRV-BANKA-MODE2") (class "Default")
      (node (ref "R43") (pin "2") (pinfunction "2_2") (pintype "passive"))
    )
    (net (code "27") (name "/DRV-BANKA-STEP-0") (class "Default")
      (node (ref "U2") (pin "165") (pinfunction "PD1_165") (pintype "bidirectional"))
    )
    (net (code "28") (name "/DRV-BANKA-STEP-1") (class "Default")
      (node (ref "U2") (pin "167") (pinfunction "PD3_167") (pintype "bidirectional"))
    )
    (net (code "29") (name "/DRV-BANKA-STEP-2") (class "Default")
      (node (ref "U2") (pin "169") (pinfunction "PD5_169") (pintype "bidirectional"))
    )
    (net (code "30") (name "/DRV-BANKA-STEP-3") (class "Default")
      (node (ref "U2") (pin "173") (pinfunction "PD7_173") (pintype "bidirectional"))
    )
    (net (code "31") (name "/DRV-BANKA-STEP-4") (class "Default")
      (node (ref "U2") (pin "109") (pinfunction "PD9_109") (pintype "bidirectional"))
    )
    (net (code "32") (name "/DRV-BANKA-STEP-5") (class "Default")
      (node (ref "U2") (pin "111") (pinfunction "PD11_111") (pintype "bidirectional"))
    )
    (net (code "33") (name "/DRV-BANKA-STEP-6") (class "Default")
      (node (ref "U2") (pin "113") (pinfunction "PD13_113") (pintype "bidirectional"))
    )
    (net (code "34") (name "/DRV-BANKA-STEP-7") (class "Default")
      (node (ref "U2") (pin "117") (pinfunction "PD15_117") (pintype "bidirectional"))
    )
    (net (code "36") (name "/DRV-BANKA-VREF") (class "Default")
      (node (ref "R31") (pin "1") (pinfunction "1_1") (pintype "passive"))
    )
    (net (code "37") (name "/DRV-BANKA-nENBL") (class "Default")
      (node (ref "U2") (pin "102") (pinfunction "PH12_102") (pintype "bidirectional+no_connect"))
    )
    (net (code "38") (name "/DRV-BANKA-nFAULT") (class "Default")
      (node (ref "U2") (pin "161") (pinfunction "PC10_161") (pintype "bidirectional+no_connect"))
    )
    (net (code "39") (name "/DRV-BANKA-nRESET") (class "Default")
      (node (ref "U2") (pin "98") (pinfunction "PH8_98") (pintype "bidirectional+no_connect"))
    )
    (net (code "40") (name "/DRV-BANKABCD-DECAY") (class "Default")
      (node (ref "R48") (pin "1") (pinfunction "1_1") (pintype "passive"))
      (node (ref "R49") (pin "1") (pinfunction "1_1") (pintype "passive"))
      (node (ref "R50") (pin "1") (pinfunction "1_1") (pintype "passive"))
      (node (ref "U2") (pin "49") (pinfunction "PH5_49") (pintype "bidirectional"))
    )
    (net (code "41") (name "/DRV-BANKABCD-MODE0") (class "Default")
      (node (ref "R35") (pin "1") (pinfunction "1_1") (pintype "passive"))
      (node (ref "R36") (pin "1") (pinfunction "1_1") (pintype "passive"))
      (node (ref "R37") (pin "1") (pinfunction "1_1") (pintype "passive"))
      (node (ref "U2") (pin "46") (pinfunction "PH2_46") (pintype "bidirectional"))
    )
    (net (code "42") (name "/DRV-BANKABCD-MODE1") (class "Default")
      (node (ref "R39") (pin "1") (pinfunction "1_1") (pintype "passive"))
      (node (ref "R40") (pin "1") (pinfunction "1_1") (pintype "passive"))
      (node (ref "R41") (pin "1") (pinfunction "1_1") (pintype "passive"))
      (node (ref "U2") (pin "47") (pinfunction "PH3_47") (pintype "bidirectional"))
    )
    (net (code "43") (name "/DRV-BANKABCD-MODE2") (class "Default")
      (node (ref "R43") (pin "1") (pinfunction "1_1") (pintype "passive"))
      (node (ref "R44") (pin "1") (pinfunction "1_1") (pintype "passive"))
      (node (ref "R45") (pin "1") (pinfunction "1_1") (pintype "passive"))
      (node (ref "U2") (pin "48") (pinfunction "PH4_48") (pintype "bidirectional"))
    )
    (net (code "44") (name "/DRV-BANKABCD-VREF") (class "Default")
      (node (ref "R31") (pin "2") (pinfunction "2_2") (pintype "passive"))
      (node (ref "R32") (pin "2") (pinfunction "2_2") (pintype "passive"))
      (node (ref "R33") (pin "2") (pinfunction "2_2") (pintype "passive"))
      (node (ref "U2") (pin "53") (pinfunction "PA4_53") (pintype "bidirectional"))
    )
    (net (code "45") (name "/DRV-BANKB-DECAY") (class "Default")
      (node (ref "R49") (pin "2") (pinfunction "2_2") (pintype "passive"))
    )
    (net (code "46") (name "/DRV-BANKB-DIR-0") (class "Default")
      (node (ref "U2") (pin "200") (pinfunction "PE0_200") (pintype "bidirectional"))
    )
    (net (code "47") (name "/DRV-BANKB-DIR-1") (class "Default")
      (node (ref "U2") (pin "1") (pinfunction "PE2_1") (pintype "bidirectional"))
    )
    (net (code "48") (name "/DRV-BANKB-DIR-2") (class "Default")
      (node (ref "U2") (pin "3") (pinfunction "PE4_3") (pintype "bidirectional"))
    )
    (net (code "49") (name "/DRV-BANKB-DIR-3") (class "Default")
      (node (ref "U2") (pin "5") (pinfunction "PE6_5") (pintype "bidirectional"))
    )
    (net (code "50") (name "/DRV-BANKB-DIR-4") (class "Default")
      (node (ref "U2") (pin "80") (pinfunction "PE8_80") (pintype "bidirectional"))
    )
    (net (code "51") (name "/DRV-BANKB-DIR-5") (class "Default")
      (node (ref "U2") (pin "84") (pinfunction "PE10_84") (pintype "bidirectional"))
    )
    (net (code "52") (name "/DRV-BANKB-DIR-6") (class "Default")
      (node (ref "U2") (pin "86") (pinfunction "PE12_86") (pintype "bidirectional"))
    )
    (net (code "53") (name "/DRV-BANKB-DIR-7") (class "Default")
      (node (ref "U2") (pin "88") (pinfunction "PE14_88") (pintype "bidirectional"))
    )
    (net (code "55") (name "/DRV-BANKB-MODE0") (class "Default")
      (node (ref "R36") (pin "2") (pinfunction "2_2") (pintype "passive"))
    )
    (net (code "56") (name "/DRV-BANKB-MODE1") (class "Default")
      (node (ref "R40") (pin "2") (pinfunction "2_2") (pintype "passive"))
    )
    (net (code "57") (name "/DRV-BANKB-MODE2") (class "Default")
      (node (ref "R44") (pin "2") (pinfunction "2_2") (pintype "passive"))
    )
    (net (code "58") (name "/DRV-BANKB-STEP-0") (class "Default")
      (node (ref "U2") (pin "201") (pinfunction "PE1_201") (pintype "bidirectional"))
    )
    (net (code "59") (name "/DRV-BANKB-STEP-1") (class "Default")
      (node (ref "U2") (pin "2") (pinfunction "PE3_2") (pintype "bidirectional"))
    )
    (net (code "60") (name "/DRV-BANKB-STEP-2") (class "Default")
      (node (ref "U2") (pin "4") (pinfunction "PE5_4") (pintype "bidirectional"))
    )
    (net (code "61") (name "/DRV-BANKB-STEP-3") (class "Default")
      (node (ref "U2") (pin "79") (pinfunction "PE7_79") (pintype "bidirectional"))
    )
    (net (code "62") (name "/DRV-BANKB-STEP-4") (class "Default")
      (node (ref "U2") (pin "81") (pinfunction "PE9_81") (pintype "bidirectional"))
    )
    (net (code "63") (name "/DRV-BANKB-STEP-5") (class "Default")
      (node (ref "U2") (pin "85") (pinfunction "PE11_85") (pintype "bidirectional"))
    )
    (net (code "64") (name "/DRV-BANKB-STEP-6") (class "Default")
      (node (ref "U2") (pin "87") (pinfunction "PE13_87") (pintype "bidirectional"))
    )
    (net (code "65") (name "/DRV-BANKB-STEP-7") (class "Default")
      (node (ref "U2") (pin "89") (pinfunction "PE15_89") (pintype "bidirectional"))
    )
    (net (code "67") (name "/DRV-BANKB-VREF") (class "Default")
      (node (ref "R32") (pin "1") (pinfunction "1_1") (pintype "passive"))
    )
    (net (code "68") (name "/DRV-BANKB-nENBL") (class "Default")
      (node (ref "U2") (pin "151") (pinfunction "PH13_151") (pintype "bidirectional+no_connect"))
    )
    (net (code "69") (name "/DRV-BANKB-nFAULT") (class "Default")
      (node (ref "U2") (pin "162") (pinfunction "PC11_162") (pintype "bidirectional+no_connect"))
    )
    (net (code "70") (name "/DRV-BANKB-nRESET") (class "Default")
      (node (ref "U2") (pin "99") (pinfunction "PH9_99") (pintype "bidirectional+no_connect"))
    )
    (net (code "71") (name "/DRV-BANKC-DECAY") (class "Default")
      (node (ref "R50") (pin "2") (pinfunction "2_2") (pintype "passive"))
    )
    (net (code "72") (name "/DRV-BANKC-DIR-0") (class "Default")
      (node (ref "U2") (pin "16") (pinfunction "PF0_16") (pintype "bidirectional"))
    )
    (net (code "73") (name "/DRV-BANKC-DIR-1") (class "Default")
      (node (ref "U2") (pin "18") (pinfunction "PF2_18") (pintype "bidirectional"))
    )
    (net (code "74") (name "/DRV-BANKC-DIR-2") (class "Default")
      (node (ref "U2") (pin "23") (pinfunction "PF4_23") (pintype "bidirectional"))
    )
    (net (code "75") (name "/DRV-BANKC-DIR-3") (class "Default")
      (node (ref "U2") (pin "27") (pinfunction "PF6_27") (pintype "bidirectional"))
    )
    (net (code "76") (name "/DRV-BANKC-DIR-4") (class "Default")
      (node (ref "U2") (pin "29") (pinfunction "PF8_29") (pintype "bidirectional"))
    )
    (net (code "77") (name "/DRV-BANKC-DIR-5") (class "Default")
      (node (ref "U2") (pin "31") (pinfunction "PF10_31") (pintype "bidirectional"))
    )
    (net (code "78") (name "/DRV-BANKC-DIR-6") (class "Default")
      (node (ref "U2") (pin "71") (pinfunction "PF12_71") (pintype "bidirectional"))
    )
    (net (code "79") (name "/DRV-BANKC-DIR-7") (class "Default")
      (node (ref "U2") (pin "75") (pinfunction "PF14_75") (pintype "bidirectional"))
    )
    (net (code "81") (name "/DRV-BANKC-MODE0") (class "Default")
      (node (ref "R37") (pin "2") (pinfunction "2_2") (pintype "passive"))
    )
    (net (code "82") (name "/DRV-BANKC-MODE1") (class "Default")
      (node (ref "R41") (pin "2") (pinfunction "2_2") (pintype "passive"))
    )
    (net (code "83") (name "/DRV-BANKC-MODE2") (class "Default")
      (node (ref "R45") (pin "2") (pinfunction "2_2") (pintype "passive"))
    )
    (net (code "84") (name "/DRV-BANKC-STEP-0") (class "Default")
      (node (ref "U2") (pin "17") (pinfunction "PF1_17") (pintype "bidirectional"))
    )
    (net (code "85") (name "/DRV-BANKC-STEP-1") (class "Default")
      (node (ref "U2") (pin "22") (pinfunction "PF3_22") (pintype "bidirectional"))
    )
    (net (code "86") (name "/DRV-BANKC-STEP-2") (class "Default")
      (node (ref "U2") (pin "24") (pinfunction "PF5_24") (pintype "bidirectional"))
    )
    (net (code "87") (name "/DRV-BANKC-STEP-3") (class "Default")
      (node (ref "U2") (pin "28") (pinfunction "PF7_28") (pintype "bidirectional"))
    )
    (net (code "88") (name "/DRV-BANKC-STEP-4") (class "Default")
      (node (ref "U2") (pin "30") (pinfunction "PF9_30") (pintype "bidirectional"))
    )
    (net (code "89") (name "/DRV-BANKC-STEP-5") (class "Default")
      (node (ref "U2") (pin "70") (pinfunction "PF11_70") (pintype "bidirectional"))
    )
    (net (code "90") (name "/DRV-BANKC-STEP-6") (class "Default")
      (node (ref "U2") (pin "74") (pinfunction "PF13_74") (pintype "bidirectional"))
    )
    (net (code "91") (name "/DRV-BANKC-STEP-7") (class "Default")
      (node (ref "U2") (pin "76") (pinfunction "PF15_76") (pintype "bidirectional"))
    )
    (net (code "93") (name "/DRV-BANKC-VREF") (class "Default")
      (node (ref "R33") (pin "1") (pinfunction "1_1") (pintype "passive"))
    )
    (net (code "94") (name "/DRV-BANKC-nENBL") (class "Default")
      (node (ref "U2") (pin "152") (pinfunction "PH14_152") (pintype "bidirectional+no_connect"))
    )
    (net (code "95") (name "/DRV-BANKC-nFAULT") (class "Default")
      (node (ref "U2") (pin "163") (pinfunction "PC12_163") (pintype "bidirectional+no_connect"))
    )
    (net (code "96") (name "/DRV-BANKC-nRESET") (class "Default")
      (node (ref "U2") (pin "100") (pinfunction "PH10_100") (pintype "bidirectional+no_connect"))
    )
    (net (code "97") (name "/DRV-BANKD-DIR-0") (class "Default")
      (node (ref "J7") (pin "1") (pinfunction "1_1") (pintype "passive"))
      (node (ref "U2") (pin "77") (pinfunction "PG0_77") (pintype "bidirectional"))
    )
    (net (code "98") (name "/DRV-BANKD-DIR-1") (class "Default")
      (node (ref "J7") (pin "3") (pinfunction "3_3") (pintype "passive"))
      (node (ref "U2") (pin "129") (pinfunction "PG2_129") (pintype "bidirectional"))
    )
    (net (code "99") (name "/DRV-BANKD-DIR-2") (class "Default")
      (node (ref "J7") (pin "5") (pinfunction "5_5") (pintype "passive"))
      (node (ref "U2") (pin "131") (pinfunction "PG4_131") (pintype "bidirectional"))
    )
    (net (code "100") (name "/DRV-BANKD-DIR-3") (class "Default")
      (node (ref "J7") (pin "7") (pinfunction "7_7") (pintype "passive"))
      (node (ref "U2") (pin "133") (pinfunction "PG6_133") (pintype "bidirectional"))
    )
    (net (code "101") (name "/DRV-BANKD-DIR-4") (class "Default")
      (node (ref "U2") (pin "135") (pinfunction "PG8_135") (pintype "bidirectional+no_connect"))
    )
    (net (code "102") (name "/DRV-BANKD-DIR-5") (class "Default")
      (node (ref "U2") (pin "179") (pinfunction "PG10_179") (pintype "bidirectional+no_connect"))
    )
    (net (code "103") (name "/DRV-BANKD-DIR-6") (class "Default")
      (node (ref "U2") (pin "181") (pinfunction "PG12_181") (pintype "bidirectional+no_connect"))
    )
    (net (code "104") (name "/DRV-BANKD-DIR-7") (class "Default")
      (node (ref "U2") (pin "183") (pinfunction "PG14_183") (pintype "bidirectional+no_connect"))
    )
    (net (code "105") (name "/DRV-BANKD-STEP-0") (class "Default")
      (node (ref "J7") (pin "2") (pinfunction "2_2") (pintype "passive"))
      (node (ref "U2") (pin "78") (pinfunction "PG1_78") (pintype "bidirectional"))
    )
    (net (code "106") (name "/DRV-BANKD-STEP-1") (class "Default")
      (node (ref "J7") (pin "4") (pinfunction "4_4") (pintype "passive"))
      (node (ref "U2") (pin "130") (pinfunction "PG3_130") (pintype "bidirectional"))
    )
    (net (code "107") (name "/DRV-BANKD-STEP-2") (class "Default")
      (node (ref "J7") (pin "6") (pinfunction "6_6") (pintype "passive"))
      (node (ref "U2") (pin "132") (pinfunction "PG5_132") (pintype "bidirectional"))
    )
    (net (code "108") (name "/DRV-BANKD-STEP-3") (class "Default")
      (node (ref "J7") (pin "8") (pinfunction "8_8") (pintype "passive"))
      (node (ref "U2") (pin "134") (pinfunction "PG7_134") (pintype "bidirectional"))
    )
    (net (code "109") (name "/DRV-BANKD-STEP-4") (class "Default")
      (node (ref "U2") (pin "178") (pinfunction "PG9_178") (pintype "bidirectional+no_connect"))
    )
    (net (code "110") (name "/DRV-BANKD-STEP-5") (class "Default")
      (node (ref "U2") (pin "180") (pinfunction "PG11_180") (pintype "bidirectional+no_connect"))
    )
    (net (code "111") (name "/DRV-BANKD-STEP-6") (class "Default")
      (node (ref "U2") (pin "182") (pinfunction "PG13_182") (pintype "bidirectional+no_connect"))
    )
    (net (code "112") (name "/DRV-BANKD-STEP-7") (class "Default")
      (node (ref "U2") (pin "191") (pinfunction "PG15_191") (pintype "bidirectional+no_connect"))
    )
    (net (code "113") (name "/DRV-BANKD-nENBL") (class "Default")
      (node (ref "U2") (pin "153") (pinfunction "PH15_153") (pintype "bidirectional+no_connect"))
    )
    (net (code "114") (name "/DRV-BANKD-nFAULT") (class "Default")
      (node (ref "U2") (pin "8") (pinfunction "PC13_8") (pintype "bidirectional+no_connect"))
    )
    (net (code "115") (name "/DRV-BANKD-nRESET") (class "Default")
      (node (ref "U2") (pin "101") (pinfunction "PH11_101") (pintype "bidirectional+no_connect"))
    )
    (net (code "116") (name "/ETH-CRS-DV") (class "Default")
      (node (ref "U2") (pin "56") (pinfunction "PA7_56") (pintype "bidirectional+no_connect"))
    )
    (net (code "117") (name "/ETH-MDC") (class "Default")
      (node (ref "U2") (pin "36") (pinfunction "PC1_36") (pintype "bidirectional+no_connect"))
    )
    (net (code "118") (name "/ETH-MDIO") (class "Default")
      (node (ref "U2") (pin "45") (pinfunction "PA2_45") (pintype "bidirectional+no_connect"))
    )
    (net (code "119") (name "/ETH-REF-CLK") (class "Default")
      (node (ref "U2") (pin "44") (pinfunction "PA1_44") (pintype "bidirectional+no_connect"))
    )
    (net (code "120") (name "/ETH-RXD0") (class "Default")
      (node (ref "U2") (pin "57") (pinfunction "PC4_57") (pintype "bidirectional+no_connect"))
    )
    (net (code "121") (name "/ETH-RXD1") (class "Default")
      (node (ref "U2") (pin "58") (pinfunction "PC5_58") (pintype "bidirectional+no_connect"))
    )
    (net (code "122") (name "/ETH-TX-EN") (class "Default")
      (node (ref "U2") (pin "91") (pinfunction "PB11_91") (pintype "bidirectional+no_connect"))
    )
    (net (code "123") (name "/ETH-TXD0") (class "Default")
      (node (ref "U2") (pin "104") (pinfunction "PB12_104") (pintype "bidirectional+no_connect"))
    )
    (net (code "124") (name "/ETH-TXD1") (class "Default")
      (node (ref "U2") (pin "105") (pinfunction "PB13_105") (pintype "bidirectional+no_connect"))
    )
    (net (code "125") (name "/I2C-SCL") (class "Default")
      (node (ref "R71") (pin "1") (pinfunction "1_1") (pintype "passive"))
      (node (ref "TP2") (pin "1") (pinfunction "1_1") (pintype "passive"))
      (node (ref "U2") (pin "198") (pinfunction "PB8_198") (pintype "bidirectional"))
      (node (ref "U7") (pin "1") (pinfunction "SCL_1") (pintype "passive"))
    )
    (net (code "126") (name "/I2C-SDA") (class "Default")
      (node (ref "R72") (pin "1") (pinfunction "1_1") (pintype "passive"))
      (node (ref "TP4") (pin "1") (pinfunction "1_1") (pintype "passive"))
      (node (ref "U2") (pin "199") (pinfunction "PB9_199") (pintype "bidirectional"))
      (node (ref "U7") (pin "3") (pinfunction "SDA_3") (pintype "passive"))
    )
    (net (code "127") (name "/JTAG.NRST") (class "Default")
      (node (ref "R52") (pin "2") (pinfunction "2_2") (pintype "passive"))
      (node (ref "R55") (pin "1") (pinfunction "1_1") (pintype "passive"))
    )
    (net (code "128") (name "/JTAG.TCK") (class "Default")
      (node (ref "R51") (pin "1") (pinfunction "1_1") (pintype "passive"))
      (node (ref "R64") (pin "2") (pinfunction "2_2") (pintype "passive"))
      (node (ref "U2") (pin "159") (pinfunction "PA14(JTCK-SWCLK)_159") (pintype "bidirectional"))
    )
    (net (code "129") (name "/JTAG.TDI") (class "Default")
      (node (ref "R54") (pin "1") (pinfunction "1_1") (pintype "passive"))
      (node (ref "R75") (pin "1") (pinfunction "1_1") (pintype "passive"))
      (node (ref "U2") (pin "160") (pinfunction "PA15(JTDI)_160") (pintype "bidirectional"))
    )
    (net (code "130") (name "/JTAG.TDO") (class "Default")
      (node (ref "R53") (pin "1") (pinfunction "1_1") (pintype "passive"))
      (node (ref "U2") (pin "192") (pinfunction "PB3(JTDO/TRACESWO)_192") (pintype "bidirectional"))
    )
    (net (code "131") (name "/JTAG.TMS") (class "Default")
      (node (ref "R34") (pin "1") (pinfunction "1_1") (pintype "passive"))
      (node (ref "R46") (pin "1") (pinfunction "1_1") (pintype "passive"))
      (node (ref "U2") (pin "147") (pinfunction "PA13(JTMS-SWDIO)_147") (pintype "bidirectional"))
    )
    (net (code "132") (name "/LED-B-R") (class "Default")
      (node (ref "LED1") (pin "6") (pinfunction "6_6") (pintype "passive"))
      (node (ref "R68") (pin "1") (pinfunction "1_1") (pintype "passive"))
    )
    (net (code "133") (name "/LED-BANKA-MOSI-0") (class "Default")
      (node (ref "U2") (pin "154") (pinfunction "PI0_154") (pintype "bidirectional"))
    )
    (net (code "134") (name "/LED-BANKA-MOSI-1") (class "Default")
      (node (ref "U2") (pin "155") (pinfunction "PI1_155") (pintype "bidirectional"))
    )
    (net (code "135") (name "/LED-BANKA-MOSI-2") (class "Default")
      (node (ref "U2") (pin "156") (pinfunction "PI2_156") (pintype "bidirectional"))
    )
    (net (code "136") (name "/LED-BANKA-MOSI-3") (class "Default")
      (node (ref "U2") (pin "157") (pinfunction "PI3_157") (pintype "bidirectional"))
    )
    (net (code "137") (name "/LED-BANKA-MOSI-4") (class "Default")
      (node (ref "U2") (pin "205") (pinfunction "PI4_205") (pintype "bidirectional"))
    )
    (net (code "138") (name "/LED-BANKA-MOSI-5") (class "Default")
      (node (ref "U2") (pin "206") (pinfunction "PI5_206") (pintype "bidirectional"))
    )
    (net (code "139") (name "/LED-BANKA-MOSI-6") (class "Default")
      (node (ref "U2") (pin "207") (pinfunction "PI6_207") (pintype "bidirectional"))
    )
    (net (code "140") (name "/LED-BANKA-MOSI-7") (class "Default")
      (node (ref "U2") (pin "208") (pinfunction "PI7_208") (pintype "bidirectional"))
    )
    (net (code "142") (name "/LED-BANKA-nOE") (class "Default")
      (node (ref "U2") (pin "138") (pinfunction "PC6_138") (pintype "bidirectional+no_connect"))
    )
    (net (code "143") (name "/LED-BANKB-MOSI-0") (class "Default")
      (node (ref "U2") (pin "7") (pinfunction "PI8_7") (pintype "bidirectional"))
    )
    (net (code "144") (name "/LED-BANKB-MOSI-1") (class "Default")
      (node (ref "U2") (pin "11") (pinfunction "PI9_11") (pintype "bidirectional"))
    )
    (net (code "145") (name "/LED-BANKB-MOSI-2") (class "Default")
      (node (ref "U2") (pin "12") (pinfunction "PI10_12") (pintype "bidirectional"))
    )
    (net (code "146") (name "/LED-BANKB-MOSI-3") (class "Default")
      (node (ref "U2") (pin "13") (pinfunction "PI11_13") (pintype "bidirectional"))
    )
    (net (code "147") (name "/LED-BANKB-MOSI-4") (class "Default")
      (node (ref "U2") (pin "19") (pinfunction "PI12_19") (pintype "bidirectional"))
    )
    (net (code "148") (name "/LED-BANKB-MOSI-5") (class "Default")
      (node (ref "U2") (pin "20") (pinfunction "PI13_20") (pintype "bidirectional"))
    )
    (net (code "149") (name "/LED-BANKB-MOSI-6") (class "Default")
      (node (ref "U2") (pin "21") (pinfunction "PI14_21") (pintype "bidirectional"))
    )
    (net (code "150") (name "/LED-BANKB-MOSI-7") (class "Default")
      (node (ref "U2") (pin "64") (pinfunction "PI15_64") (pintype "bidirectional"))
    )
    (net (code "152") (name "/LED-BANKB-nOE") (class "Default")
      (node (ref "U2") (pin "139") (pinfunction "PC7_139") (pintype "bidirectional+no_connect"))
    )
    (net (code "153") (name "/LED-BANKC-MOSI-0") (class "Default")
      (node (ref "U2") (pin "65") (pinfunction "PJ0_65") (pintype "bidirectional"))
    )
    (net (code "154") (name "/LED-BANKC-MOSI-1") (class "Default")
      (node (ref "U2") (pin "66") (pinfunction "PJ1_66") (pintype "bidirectional"))
    )
    (net (code "155") (name "/LED-BANKC-MOSI-2") (class "Default")
      (node (ref "U2") (pin "67") (pinfunction "PJ2_67") (pintype "bidirectional"))
    )
    (net (code "156") (name "/LED-BANKC-MOSI-3") (class "Default")
      (node (ref "U2") (pin "68") (pinfunction "PJ3_68") (pintype "bidirectional"))
    )
    (net (code "157") (name "/LED-BANKC-MOSI-4") (class "Default")
      (node (ref "U2") (pin "69") (pinfunction "PJ4_69") (pintype "bidirectional"))
    )
    (net (code "158") (name "/LED-BANKC-MOSI-5") (class "Default")
      (node (ref "U2") (pin "95") (pinfunction "PJ5_95") (pintype "bidirectional"))
    )
    (net (code "159") (name "/LED-BANKC-MOSI-6") (class "Default")
      (node (ref "U2") (pin "118") (pinfunction "PJ6_118") (pintype "bidirectional"))
    )
    (net (code "160") (name "/LED-BANKC-MOSI-7") (class "Default")
      (node (ref "U2") (pin "119") (pinfunction "PJ7_119") (pintype "bidirectional"))
    )
    (net (code "162") (name "/LED-BANKC-nOE") (class "Default")
      (node (ref "U2") (pin "140") (pinfunction "PC8_140") (pintype "bidirectional+no_connect"))
    )
    (net (code "163") (name "/LED-BANKD-MOSI-0") (class "Default")
      (node (ref "U2") (pin "120") (pinfunction "PJ8_120") (pintype "bidirectional+no_connect"))
    )
    (net (code "164") (name "/LED-BANKD-MOSI-1") (class "Default")
      (node (ref "U2") (pin "121") (pinfunction "PJ9_121") (pintype "bidirectional+no_connect"))
    )
    (net (code "165") (name "/LED-BANKD-MOSI-2") (class "Default")
      (node (ref "U2") (pin "122") (pinfunction "PJ10_122") (pintype "bidirectional+no_connect"))
    )
    (net (code "166") (name "/LED-BANKD-MOSI-3") (class "Default")
      (node (ref "U2") (pin "123") (pinfunction "PJ11_123") (pintype "bidirectional+no_connect"))
    )
    (net (code "167") (name "/LED-BANKD-MOSI-4") (class "Default")
      (node (ref "U2") (pin "174") (pinfunction "PJ12_174") (pintype "bidirectional+no_connect"))
    )
    (net (code "168") (name "/LED-BANKD-MOSI-5") (class "Default")
      (node (ref "U2") (pin "175") (pinfunction "PJ13_175") (pintype "bidirectional+no_connect"))
    )
    (net (code "169") (name "/LED-BANKD-MOSI-6") (class "Default")
      (node (ref "U2") (pin "176") (pinfunction "PJ14_176") (pintype "bidirectional+no_connect"))
    )
    (net (code "170") (name "/LED-BANKD-MOSI-7") (class "Default")
      (node (ref "U2") (pin "177") (pinfunction "PJ15_177") (pintype "bidirectional+no_connect"))
    )
    (net (code "171") (name "/LED-BANKD-nOE") (class "Default")
      (node (ref "U2") (pin "141") (pinfunction "PC9_141") (pintype "bidirectional+no_connect"))
    )
    (net (code "172") (name "/LED-G-R") (class "Default")
      (node (ref "LED1") (pin "5") (pinfunction "5_5") (pintype "passive"))
      (node (ref "R69") (pin "2") (pinfunction "2_2") (pintype "passive"))
    )
    (net (code "173") (name "/LED-R-R") (class "Default")
      (node (ref "LED1") (pin "4") (pinfunction "4_4") (pintype "passive"))
      (node (ref "R70") (pin "1") (pinfunction "1_1") (pintype "passive"))
    )
    (net (code "174") (name "/MSYNC") (class "Default")
      (node (ref "R1") (pin "2") (pinfunction "2_2") (pintype "passive"))
      (node (ref "U2") (pin "50") (pinfunction "PA3_50") (pintype "bidirectional"))
    )
    (net (code "175") (name "/RCC-OSC-IN") (class "Default")
      (node (ref "C79") (pin "1") (pinfunction "1_1") (pintype "passive"))
      (node (ref "U2") (pin "32") (pinfunction "PH0-OSC_IN(PH0)_32") (pintype "bidirectional"))
      (node (ref "X1") (pin "3") (pinfunction "3_3") (pintype "passive"))
    )
    (net (code "176") (name "/RCC-OSC-OUT") (class "Default")
      (node (ref "C80") (pin "2") (pinfunction "2_2") (pintype "passive"))
      (node (ref "U2") (pin "33") (pinfunction "PH1-OSC_OUT(PH1)_33") (pintype "bidirectional"))
      (node (ref "X1") (pin "1") (pinfunction "OSC1_1") (pintype "passive"))
    )
    (net (code "177") (name "/SPI-MISO") (class "Default")
      (node (ref "TP6") (pin "1") (pinfunction "1_1") (pintype "passive"))
      (node (ref "U2") (pin "37") (pinfunction "PC2_37") (pintype "bidirectional"))
    )
    (net (code "178") (name "/SPI-MOSI") (class "Default")
      (node (ref "TP7") (pin "1") (pinfunction "1_1") (pintype "passive"))
      (node (ref "U2") (pin "38") (pinfunction "PC3_38") (pintype "bidirectional"))
    )
    (net (code "179") (name "/SPI-NSS") (class "Default")
      (node (ref "TP15") (pin "1") (pinfunction "1_1") (pintype "passive"))
      (node (ref "U2") (pin "193") (pinfunction "PB4(NJTRST)_193") (pintype "bidirectional"))
    )
    (net (code "180") (name "/SPI-SCK") (class "Default")
      (node (ref "TP5") (pin "1") (pinfunction "1_1") (pintype "passive"))
      (node (ref "U2") (pin "90") (pinfunction "PB10_90") (pintype "bidirectional"))
    )
    (net (code "181") (name "/SSYNC") (class "Default")
      (node (ref "R30") (pin "2") (pinfunction "2_2") (pintype "passive"))
      (node (ref "U2") (pin "43") (pinfunction "PA0-WKUP(PA0)_43") (pintype "bidirectional"))
      (node (ref "U5") (pin "4") (pinfunction "Y_4") (pintype "passive"))
    )
    (net (code "182") (name "/SSYNC-EXT") (class "Default")
      (node (ref "J10") (pin "2") (pinfunction "2_2") (pintype "passive"))
      (node (ref "R56") (pin "2") (pinfunction "2_2") (pintype "passive"))
    )
    (net (code "183") (name "/SSYNC-EXT-GND") (class "Default")
      (node (ref "J10") (pin "3") (pinfunction "3_3") (pintype "passive"))
      (node (ref "OPTO1") (pin "3") (pinfunction "LED_K_3") (pintype "passive"))
    )
    (net (code "184") (name "/SSYNC-OPTO-R") (class "Default")
      (node (ref "OPTO1") (pin "1") (pinfunction "LED_A_1") (pintype "passive"))
      (node (ref "R56") (pin "1") (pinfunction "1_1") (pintype "passive"))
    )
    (net (code "185") (name "/STAT-LED-B") (class "Default")
      (node (ref "R67") (pin "2") (pinfunction "2_2") (pintype "passive"))
      (node (ref "U2") (pin "107") (pinfunction "PB15_107") (pintype "bidirectional"))
    )
    (net (code "186") (name "/STAT-LED-B-R") (class "Default")
      (node (ref "LED2") (pin "6") (pinfunction "6_6") (pintype "passive"))
      (node (ref "R67") (pin "1") (pinfunction "1_1") (pintype "passive"))
    )
    (net (code "187") (name "/STAT-LED-G") (class "Default")
      (node (ref "R73") (pin "1") (pinfunction "1_1") (pintype "passive"))
      (node (ref "U2") (pin "63") (pinfunction "PB2_63") (pintype "bidirectional"))
    )
    (net (code "188") (name "/STAT-LED-G-R") (class "Default")
      (node (ref "LED2") (pin "5") (pinfunction "5_5") (pintype "passive"))
      (node (ref "R73") (pin "2") (pinfunction "2_2") (pintype "passive"))
    )
    (net (code "189") (name "/STAT-LED-R") (class "Default")
      (node (ref "R74") (pin "2") (pinfunction "2_2") (pintype "passive"))
      (node (ref "U2") (pin "62") (pinfunction "PB1_62") (pintype "bidirectional"))
    )
    (net (code "190") (name "/STAT-LED-R-R") (class "Default")
      (node (ref "LED2") (pin "4") (pinfunction "4_4") (pintype "passive"))
      (node (ref "R74") (pin "1") (pinfunction "1_1") (pintype "passive"))
    )
    (net (code "191") (name "/UART-RX") (class "Default")
      (node (ref "R65") (pin "1") (pinfunction "1_1") (pintype "passive"))
      (node (ref "U2") (pin "194") (pinfunction "PB5_194") (pintype "bidirectional"))
    )
    (net (code "192") (name "/UART-TX") (class "Default")
      (node (ref "R66") (pin "1") (pinfunction "1_1") (pintype "passive"))
      (node (ref "U2") (pin "195") (pinfunction "PB6_195") (pintype "bidirectional"))
    )
    (net (code "193") (name "/USB-FS-D_N") (class "Default")
      (node (ref "D8") (pin "3") (pinfunction "3_3") (pintype "passive"))
      (node (ref "D8") (pin "4") (pinfunction "4_4") (pintype "passive"))
      (node (ref "J5") (pin "2") (pinfunction "D-_2") (pintype "passive"))
      (node (ref "U2") (pin "145") (pinfunction "PA11_145") (pintype "bidirectional"))
    )
    (net (code "194") (name "/USB-FS-D_P") (class "Default")
      (node (ref "D8") (pin "1") (pinfunction "1_1") (pintype "passive"))
      (node (ref "D8") (pin "6") (pinfunction "6_6") (pintype "passive"))
      (node (ref "J5") (pin "3") (pinfunction "D+_3") (pintype "passive"))
      (node (ref "U2") (pin "146") (pinfunction "PA12_146") (pintype "bidirectional"))
    )
    (net (code "195") (name "/USB-FS-ID") (class "Default")
      (node (ref "U2") (pin "144") (pinfunction "PA10_144") (pintype "bidirectional+no_connect"))
    )
    (net (code "196") (name "/USB-FS-SOF") (class "Default")
      (node (ref "U2") (pin "142") (pinfunction "PA8_142") (pintype "bidirectional+no_connect"))
    )
    (net (code "197") (name "/USB-FS-VBUS") (class "Default")
      (node (ref "C77") (pin "1") (pinfunction "1_1") (pintype "passive"))
      (node (ref "D8") (pin "5") (pinfunction "5_5") (pintype "passive"))
      (node (ref "J5") (pin "1") (pinfunction "VCC_1") (pintype "passive"))
      (node (ref "U2") (pin "143") (pinfunction "PA9_143") (pintype "bidirectional"))
    )
    (net (code "198") (name "/VCAP_1") (class "Default")
      (node (ref "C32") (pin "1") (pinfunction "1_1") (pintype "passive"))
      (node (ref "U2") (pin "92") (pinfunction "VCAP_1_92") (pintype "power_in"))
    )
    (net (code "199") (name "/VCAP_2") (class "Default")
      (node (ref "C33") (pin "1") (pinfunction "1_1") (pintype "passive"))
      (node (ref "U2") (pin "148") (pinfunction "VCAP_2_148") (pintype "power_in"))
    )
    (net (code "200") (name "/nRST") (class "Default")
      (node (ref "C31") (pin "2") (pinfunction "2_2") (pintype "passive"))
      (node (ref "R27") (pin "1") (pinfunction "1_1") (pintype "passive"))
      (node (ref "R52") (pin "1") (pinfunction "1_1") (pintype "passive"))
      (node (ref "U2") (pin "34") (pinfunction "NRST_34") (pintype "bidirectional"))
    )
    (net (code "201") (name "AVDD-3V3") (class "Default")
      (node (ref "C34") (pin "1") (pinfunction "1_1") (pintype "passive"))
      (node (ref "L1") (pin "2") (pinfunction "2_2") (pintype "passive"))
      (node (ref "U2") (pin "41") (pinfunction "VREF+_41") (pintype "power_in"))
      (node (ref "U2") (pin "42") (pinfunction "VDDA_42") (pintype "power_in"))
    )
    (net (code "202") (name "DGND") (class "Default")
      (node (ref "C15") (pin "1") (pinfunction "1_1") (pintype "passive"))
      (node (ref "C16") (pin "2") (pinfunction "2_2") (pintype "passive"))
      (node (ref "C17") (pin "2") (pinfunction "2_2") (pintype "passive"))
      (node (ref "C18") (pin "2") (pinfunction "2_2") (pintype "passive"))
      (node (ref "C19") (pin "2") (pinfunction "2_2") (pintype "passive"))
      (node (ref "C2") (pin "2") (pinfunction "2_2") (pintype "passive"))
      (node (ref "C20") (pin "2") (pinfunction "2_2") (pintype "passive"))
      (node (ref "C21") (pin "2") (pinfunction "2_2") (pintype "passive"))
      (node (ref "C22") (pin "2") (pinfunction "2_2") (pintype "passive"))
      (node (ref "C23") (pin "2") (pinfunction "2_2") (pintype "passive"))
      (node (ref "C24") (pin "2") (pinfunction "2_2") (pintype "passive"))
      (node (ref "C25") (pin "2") (pinfunction "2_2") (pintype "passive"))
      (node (ref "C26") (pin "2") (pinfunction "2_2") (pintype "passive"))
      (node (ref "C27") (pin "2") (pinfunction "2_2") (pintype "passive"))
      (node (ref "C28") (pin "2") (pinfunction "2_2") (pintype "passive"))
      (node (ref "C29") (pin "2") (pinfunction "2_2") (pintype "passive"))
      (node (ref "C30") (pin "2") (pinfunction "2_2") (pintype "passive"))
      (node (ref "C31") (pin "1") (pinfunction "1_1") (pintype "passive"))
      (node (ref "C32") (pin "2") (pinfunction "2_2") (pintype "passive"))
      (node (ref "C33") (pin "2") (pinfunction "2_2") (pintype "passive"))
      (node (ref "C34") (pin "2") (pinfunction "2_2") (pintype "passive"))
      (node (ref "C55") (pin "2") (pinfunction "2_2") (pintype "passive"))
      (node (ref "C7") (pin "2") (pinfunction "2_2") (pintype "passive"))
      (node (ref "C76") (pin "2") (pinfunction "2_2") (pintype "passive"))
      (node (ref "C77") (pin "2") (pinfunction "2_2") (pintype "passive"))
      (node (ref "C79") (pin "2") (pinfunction "2_2") (pintype "passive"))
      (node (ref "C80") (pin "1") (pinfunction "1_1") (pintype "passive"))
      (node (ref "D8") (pin "2") (pinfunction "2_2") (pintype "passive"))
      (node (ref "J2") (pin "3") (pinfunction "GND_3") (pintype "passive"))
      (node (ref "J2") (pin "5") (pinfunction "GND_5") (pintype "passive"))
      (node (ref "J2") (pin "9") (pinfunction "GNDdet_9") (pintype "passive"))
      (node (ref "J5") (pin "10") (pinfunction "MECH_10") (pintype "passive"))
      (node (ref "J5") (pin "11") (pinfunction "MECH_11") (pintype "passive"))
      (node (ref "J5") (pin "5") (pinfunction "GND_5") (pintype "passive"))
      (node (ref "J5") (pin "6") (pinfunction "MECH_6") (pintype "passive"))
      (node (ref "J5") (pin "7") (pinfunction "MECH_7") (pintype "passive"))
      (node (ref "J5") (pin "8") (pinfunction "MECH_8") (pintype "passive"))
      (node (ref "J5") (pin "9") (pinfunction "MECH_9") (pintype "passive"))
      (node (ref "J6") (pin "1") (pinfunction "GND_1") (pintype "passive"))
      (node (ref "J9") (pin "3") (pinfunction "3_3") (pintype "passive"))
      (node (ref "LED1") (pin "1") (pinfunction "1_1") (pintype "passive"))
      (node (ref "LED1") (pin "2") (pinfunction "2_2") (pintype "passive"))
      (node (ref "LED1") (pin "3") (pinfunction "3_3") (pintype "passive"))
      (node (ref "LED2") (pin "1") (pinfunction "1_1") (pintype "passive"))
      (node (ref "LED2") (pin "2") (pinfunction "2_2") (pintype "passive"))
      (node (ref "LED2") (pin "3") (pinfunction "3_3") (pintype "passive"))
      (node (ref "OPTO1") (pin "4") (pinfunction "GND_4") (pintype "passive"))
      (node (ref "R29") (pin "1") (pinfunction "1_1") (pintype "passive"))
      (node (ref "R64") (pin "1") (pinfunction "1_1") (pintype "passive"))
      (node (ref "SW1") (pin "1") (pinfunction "1_1") (pintype "passive"))
      (node (ref "SW1") (pin "2") (pinfunction "2_2") (pintype "passive"))
      (node (ref "SW1") (pin "3") (pinfunction "3_3") (pintype "passive"))
      (node (ref "SW1") (pin "4") (pinfunction "4_4") (pintype "passive"))
      (node (ref "SW1") (pin "5") (pinfunction "5_5") (pintype "passive"))
      (node (ref "SW1") (pin "6") (pinfunction "6_6") (pintype "passive"))
      (node (ref "SW1") (pin "7") (pinfunction "7_7") (pintype "passive"))
      (node (ref "SW1") (pin "8") (pinfunction "8_8") (pintype "passive"))
      (node (ref "SW2") (pin "3") (pinfunction "3_3") (pintype "passive"))
      (node (ref "SW2") (pin "4") (pinfunction "4_4") (pintype "passive"))
      (node (ref "SW3") (pin "3") (pinfunction "3_3") (pintype "passive"))
      (node (ref "SW3") (pin "4") (pinfunction "4_4") (pintype "passive"))
      (node (ref "U2") (pin "114") (pinfunction "VSS_114") (pintype "power_in"))
      (node (ref "U2") (pin "125") (pinfunction "VSS_125") (pintype "power_in"))
      (node (ref "U2") (pin "136") (pinfunction "VSS_136") (pintype "power_in"))
      (node (ref "U2") (pin "14") (pinfunction "VSS_14") (pintype "power_in"))
      (node (ref "U2") (pin "149") (pinfunction "VSS_149") (pintype "power_in"))
      (node (ref "U2") (pin "170") (pinfunction "VSS_170") (pintype "power_in"))
      (node (ref "U2") (pin "184") (pinfunction "VSS_184") (pintype "power_in"))
      (node (ref "U2") (pin "202") (pinfunction "VSS_202") (pintype "power_in"))
      (node (ref "U2") (pin "25") (pinfunction "VSS_25") (pintype "power_in"))
      (node (ref "U2") (pin "40") (pinfunction "VSSA_40") (pintype "power_in"))
      (node (ref "U2") (pin "51") (pinfunction "VSS_51") (pintype "power_in"))
      (node (ref "U2") (pin "60") (pinfunction "VSS_60") (pintype "power_in"))
      (node (ref "U2") (pin "72") (pinfunction "VSS_72") (pintype "power_in"))
      (node (ref "U2") (pin "82") (pinfunction "VSS_82") (pintype "power_in"))
      (node (ref "U2") (pin "93") (pinfunction "VSS_93") (pintype "power_in"))
      (node (ref "U5") (pin "3") (pinfunction "GND_3") (pintype "passive"))
      (node (ref "U7") (pin "2") (pinfunction "VSS_2") (pintype "passive"))
      (node (ref "X1") (pin "2") (pinfunction "CAN_2") (pintype "passive"))
      (node (ref "X1") (pin "4") (pinfunction "CAN_4") (pintype "passive"))
    )
    (net (code "203") (name "Net-(J2-NC{slash}TDI)") (class "Default")
      (node (ref "J2") (pin "8") (pinfunction "NC/TDI_8") (pintype "passive"))
      (node (ref "R54") (pin "2") (pinfunction "2_2") (pintype "passive"))
    )
    (net (code "204") (name "Net-(J2-SWDCLK{slash}TCK)") (class "Default")
      (node (ref "J2") (pin "4") (pinfunction "SWDCLK/TCK_4") (pintype "passive"))
      (node (ref "R51") (pin "2") (pinfunction "2_2") (pintype "passive"))
    )
    (net (code "205") (name "Net-(J2-SWDIO{slash}TMS)") (class "Default")
      (node (ref "J2") (pin "2") (pinfunction "SWDIO/TMS_2") (pintype "passive"))
      (node (ref "R46") (pin "2") (pinfunction "2_2") (pintype "passive"))
    )
    (net (code "206") (name "Net-(J2-SWO{slash}TDO)") (class "Default")
      (node (ref "J2") (pin "6") (pinfunction "SWO/TDO_6") (pintype "passive"))
      (node (ref "R53") (pin "2") (pinfunction "2_2") (pintype "passive"))
    )
    (net (code "207") (name "Net-(J2-VCC)") (class "Default")
      (node (ref "J2") (pin "1") (pinfunction "VCC_1") (pintype "passive"))
      (node (ref "R42") (pin "1") (pinfunction "1_1") (pintype "passive"))
    )
    (net (code "208") (name "Net-(J2-nRESET)") (class "Default")
      (node (ref "J2") (pin "10") (pinfunction "nRESET_10") (pintype "passive"))
      (node (ref "R55") (pin "2") (pinfunction "2_2") (pintype "passive"))
    )
    (net (code "209") (name "Net-(J6-RXD)") (class "Default")
      (node (ref "J6") (pin "4") (pinfunction "RXD_4") (pintype "passive"))
      (node (ref "R66") (pin "2") (pinfunction "2_2") (pintype "passive"))
    )
    (net (code "210") (name "Net-(J6-TXD)") (class "Default")
      (node (ref "J6") (pin "3") (pinfunction "TXD_3") (pintype "passive"))
      (node (ref "R65") (pin "2") (pinfunction "2_2") (pintype "passive"))
    )
    (net (code "211") (name "Net-(J9-Pad2)") (class "Default")
      (node (ref "J9") (pin "2") (pinfunction "2_2") (pintype "passive"))
      (node (ref "R1") (pin "1") (pinfunction "1_1") (pintype "passive"))
      (node (ref "R30") (pin "1") (pinfunction "1_1") (pintype "passive"))
    )
    (net (code "212") (name "Net-(OPTO1-V_O)") (class "Default")
      (node (ref "OPTO1") (pin "5") (pinfunction "V_O_5") (pintype "passive"))
      (node (ref "U5") (pin "2") (pinfunction "A_2") (pintype "passive"))
    )
    (net (code "213") (name "Net-(R17-Pad1)") (class "Default")
      (node (ref "R17") (pin "1") (pinfunction "1_1") (pintype "passive"))
      (node (ref "R18") (pin "2") (pinfunction "2_2") (pintype "passive"))
      (node (ref "SW2") (pin "1") (pinfunction "1_1") (pintype "passive"))
      (node (ref "SW2") (pin "2") (pinfunction "2_2") (pintype "passive"))
    )
    (net (code "214") (name "Net-(R19-Pad1)") (class "Default")
      (node (ref "R19") (pin "1") (pinfunction "1_1") (pintype "passive"))
      (node (ref "R27") (pin "2") (pinfunction "2_2") (pintype "passive"))
      (node (ref "SW3") (pin "1") (pinfunction "1_1") (pintype "passive"))
      (node (ref "SW3") (pin "2") (pinfunction "2_2") (pintype "passive"))
    )
    (net (code "215") (name "Net-(R28-Pad1)") (class "Default")
      (node (ref "R28") (pin "1") (pinfunction "1_1") (pintype "passive"))
      (node (ref "SW4") (pin "3") (pinfunction "3_3") (pintype "passive"))
      (node (ref "SW4") (pin "4") (pinfunction "4_4") (pintype "passive"))
    )
    (net (code "216") (name "P3V3") (class "Default")
      (node (ref "C16") (pin "1") (pinfunction "1_1") (pintype "passive"))
      (node (ref "C17") (pin "1") (pinfunction "1_1") (pintype "passive"))
      (node (ref "C18") (pin "1") (pinfunction "1_1") (pintype "passive"))
      (node (ref "C19") (pin "1") (pinfunction "1_1") (pintype "passive"))
      (node (ref "C2") (pin "1") (pinfunction "1_1") (pintype "passive"))
      (node (ref "C20") (pin "1") (pinfunction "1_1") (pintype "passive"))
      (node (ref "C21") (pin "1") (pinfunction "1_1") (pintype "passive"))
      (node (ref "C22") (pin "1") (pinfunction "1_1") (pintype "passive"))
      (node (ref "C23") (pin "1") (pinfunction "1_1") (pintype "passive"))
      (node (ref "C24") (pin "1") (pinfunction "1_1") (pintype "passive"))
      (node (ref "C25") (pin "1") (pinfunction "1_1") (pintype "passive"))
      (node (ref "C26") (pin "1") (pinfunction "1_1") (pintype "passive"))
      (node (ref "C27") (pin "1") (pinfunction "1_1") (pintype "passive"))
      (node (ref "C28") (pin "1") (pinfunction "1_1") (pintype "passive"))
      (node (ref "C29") (pin "1") (pinfunction "1_1") (pintype "passive"))
      (node (ref "C30") (pin "1") (pinfunction "1_1") (pintype "passive"))
      (node (ref "C55") (pin "1") (pinfunction "1_1") (pintype "passive"))
      (node (ref "C7") (pin "1") (pinfunction "1_1") (pintype "passive"))
      (node (ref "C76") (pin "1") (pinfunction "1_1") (pintype "passive"))
      (node (ref "J6") (pin "2") (pinfunction "VCC_2") (pintype "passive"))
      (node (ref "L1") (pin "1") (pinfunction "1_1") (pintype "passive"))
      (node (ref "OPTO1") (pin "6") (pinfunction "VCC_6") (pintype "passive"))
      (node (ref "R17") (pin "2") (pinfunction "2_2") (pintype "passive"))
      (node (ref "R19") (pin "2") (pinfunction "2_2") (pintype "passive"))
      (node (ref "R28") (pin "2") (pinfunction "2_2") (pintype "passive"))
      (node (ref "R34") (pin "2") (pinfunction "2_2") (pintype "passive"))
      (node (ref "R42") (pin "2") (pinfunction "2_2") (pintype "passive"))
      (node (ref "R71") (pin "2") (pinfunction "2_2") (pintype "passive"))
      (node (ref "R72") (pin "2") (pinfunction "2_2") (pintype "passive"))
      (node (ref "R75") (pin "2") (pinfunction "2_2") (pintype "passive"))
      (node (ref "U2") (pin "103") (pinfunction "VDD_103") (pintype "power_in"))
      (node (ref "U2") (pin "115") (pinfunction "VDD_115") (pintype "power_in"))
      (node (ref "U2") (pin "124") (pinfunction "VDD_124") (pintype "power_in"))
      (node (ref "U2") (pin "137") (pinfunction "VDDUSB_137") (pintype "power_in"))
      (node (ref "U2") (pin "15") (pinfunction "VDD_15") (pintype "power_in"))
      (node (ref "U2") (pin "150") (pinfunction "VDD_150") (pintype "power_in"))
      (node (ref "U2") (pin "158") (pinfunction "VDD_158") (pintype "power_in"))
      (node (ref "U2") (pin "171") (pinfunction "VDD_171") (pintype "power_in"))
      (node (ref "U2") (pin "185") (pinfunction "VDD_185") (pintype "power_in"))
      (node (ref "U2") (pin "203") (pinfunction "PDR_ON_203") (pintype "input"))
      (node (ref "U2") (pin "204") (pinfunction "VDD_204") (pintype "power_in"))
      (node (ref "U2") (pin "26") (pinfunction "VDD_26") (pintype "power_in"))
      (node (ref "U2") (pin "39") (pinfunction "VDD_39") (pintype "power_in"))
      (node (ref "U2") (pin "52") (pinfunction "VDD_52") (pintype "power_in"))
      (node (ref "U2") (pin "59") (pinfunction "VDD_59") (pintype "power_in"))
      (node (ref "U2") (pin "6") (pinfunction "VBAT_6") (pintype "power_in"))
      (node (ref "U2") (pin "73") (pinfunction "VDD_73") (pintype "power_in"))
      (node (ref "U2") (pin "83") (pinfunction "VDD_83") (pintype "power_in"))
      (node (ref "U2") (pin "94") (pinfunction "VDD_94") (pintype "power_in"))
      (node (ref "U5") (pin "5") (pinfunction "VCC_5") (pintype "passive"))
      (node (ref "U7") (pin "4") (pinfunction "VCC_4") (pintype "passive"))
    )
    (net (code "217") (name "unconnected-(J2-KEY-Pad7)") (class "Default")
      (node (ref "J2") (pin "7") (pinfunction "KEY_7") (pintype "passive+no_connect"))
    )
    (net (code "218") (name "unconnected-(J5-ID-Pad4)") (class "Default")
      (node (ref "J5") (pin "4") (pinfunction "ID_4") (pintype "passive+no_connect"))
    )
    (net (code "219") (name "unconnected-(J9-Pad1)") (class "Default")
      (node (ref "J9") (pin "1") (pinfunction "1_1") (pintype "passive"))
    )
    (net (code "220") (name "unconnected-(J9-Pad4)") (class "Default")
      (node (ref "J9") (pin "4") (pinfunction "4_4") (pintype "passive"))
    )
    (net (code "221") (name "unconnected-(J10-Pad1)") (class "Default")
      (node (ref "J10") (pin "1") (pinfunction "1_1") (pintype "passive"))
    )
    (net (code "222") (name "unconnected-(J10-Pad4)") (class "Default")
      (node (ref "J10") (pin "4") (pinfunction "4_4") (pintype "passive"))
    )
    (net (code "223") (name "unconnected-(U2A-PA5-Pad54)") (class "Default")
      (node (ref "U2") (pin "54") (pinfunction "PA5_54") (pintype "bidirectional+no_connect"))
    )
    (net (code "224") (name "unconnected-(U2A-PA6-Pad55)") (class "Default")
      (node (ref "U2") (pin "55") (pinfunction "PA6_55") (pintype "bidirectional+no_connect"))
    )
    (net (code "225") (name "unconnected-(U2A-PC14-OSC32_IN(PC14)-Pad9)") (class "Default")
      (node (ref "U2") (pin "9") (pinfunction "PC14-OSC32_IN(PC14)_9") (pintype "bidirectional+no_connect"))
    )
    (net (code "226") (name "unconnected-(U2A-PC15-OSC32_OUT(PC15)-Pad10)") (class "Default")
      (node (ref "U2") (pin "10") (pinfunction "PC15-OSC32_OUT(PC15)_10") (pintype "bidirectional+no_connect"))
    )
    (net (code "227") (name "unconnected-(U2B-PH6-Pad96)") (class "Default")
      (node (ref "U2") (pin "96") (pinfunction "PH6_96") (pintype "bidirectional+no_connect"))
    )
    (net (code "228") (name "unconnected-(U2B-PH7-Pad97)") (class "Default")
      (node (ref "U2") (pin "97") (pinfunction "PH7_97") (pintype "bidirectional+no_connect"))
    )
    (net (code "229") (name "unconnected-(U5-N{slash}C-Pad1)") (class "Default")
      (node (ref "U5") (pin "1") (pinfunction "N/C_1") (pintype "passive"))
    )
    (net (code "230") (name "unconnected-(U7-N{slash}C-Pad5)") (class "Default")
      (node (ref "U7") (pin "5") (pinfunction "N/C_5") (pintype "passive+no_connect"))
    )
  )
)
